# io-board-d-1.net
KiCad netlist of a schematic drawn in EAGLE
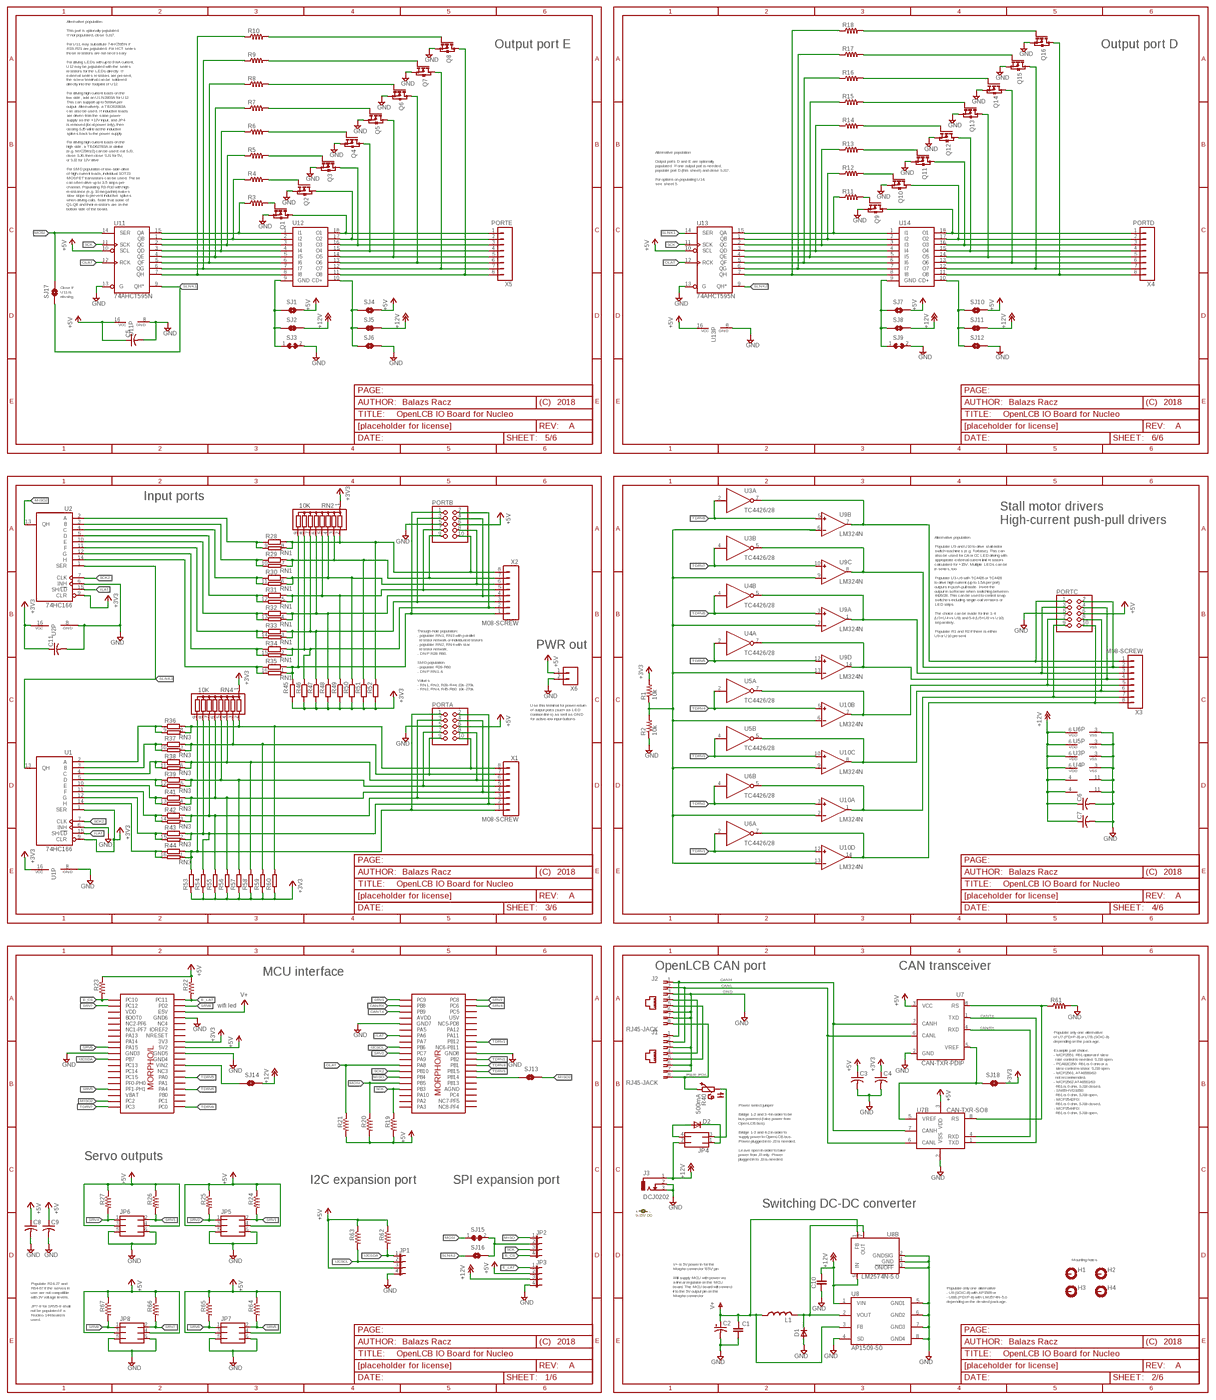
[diagram p0: schematic, sheet 1, overview]
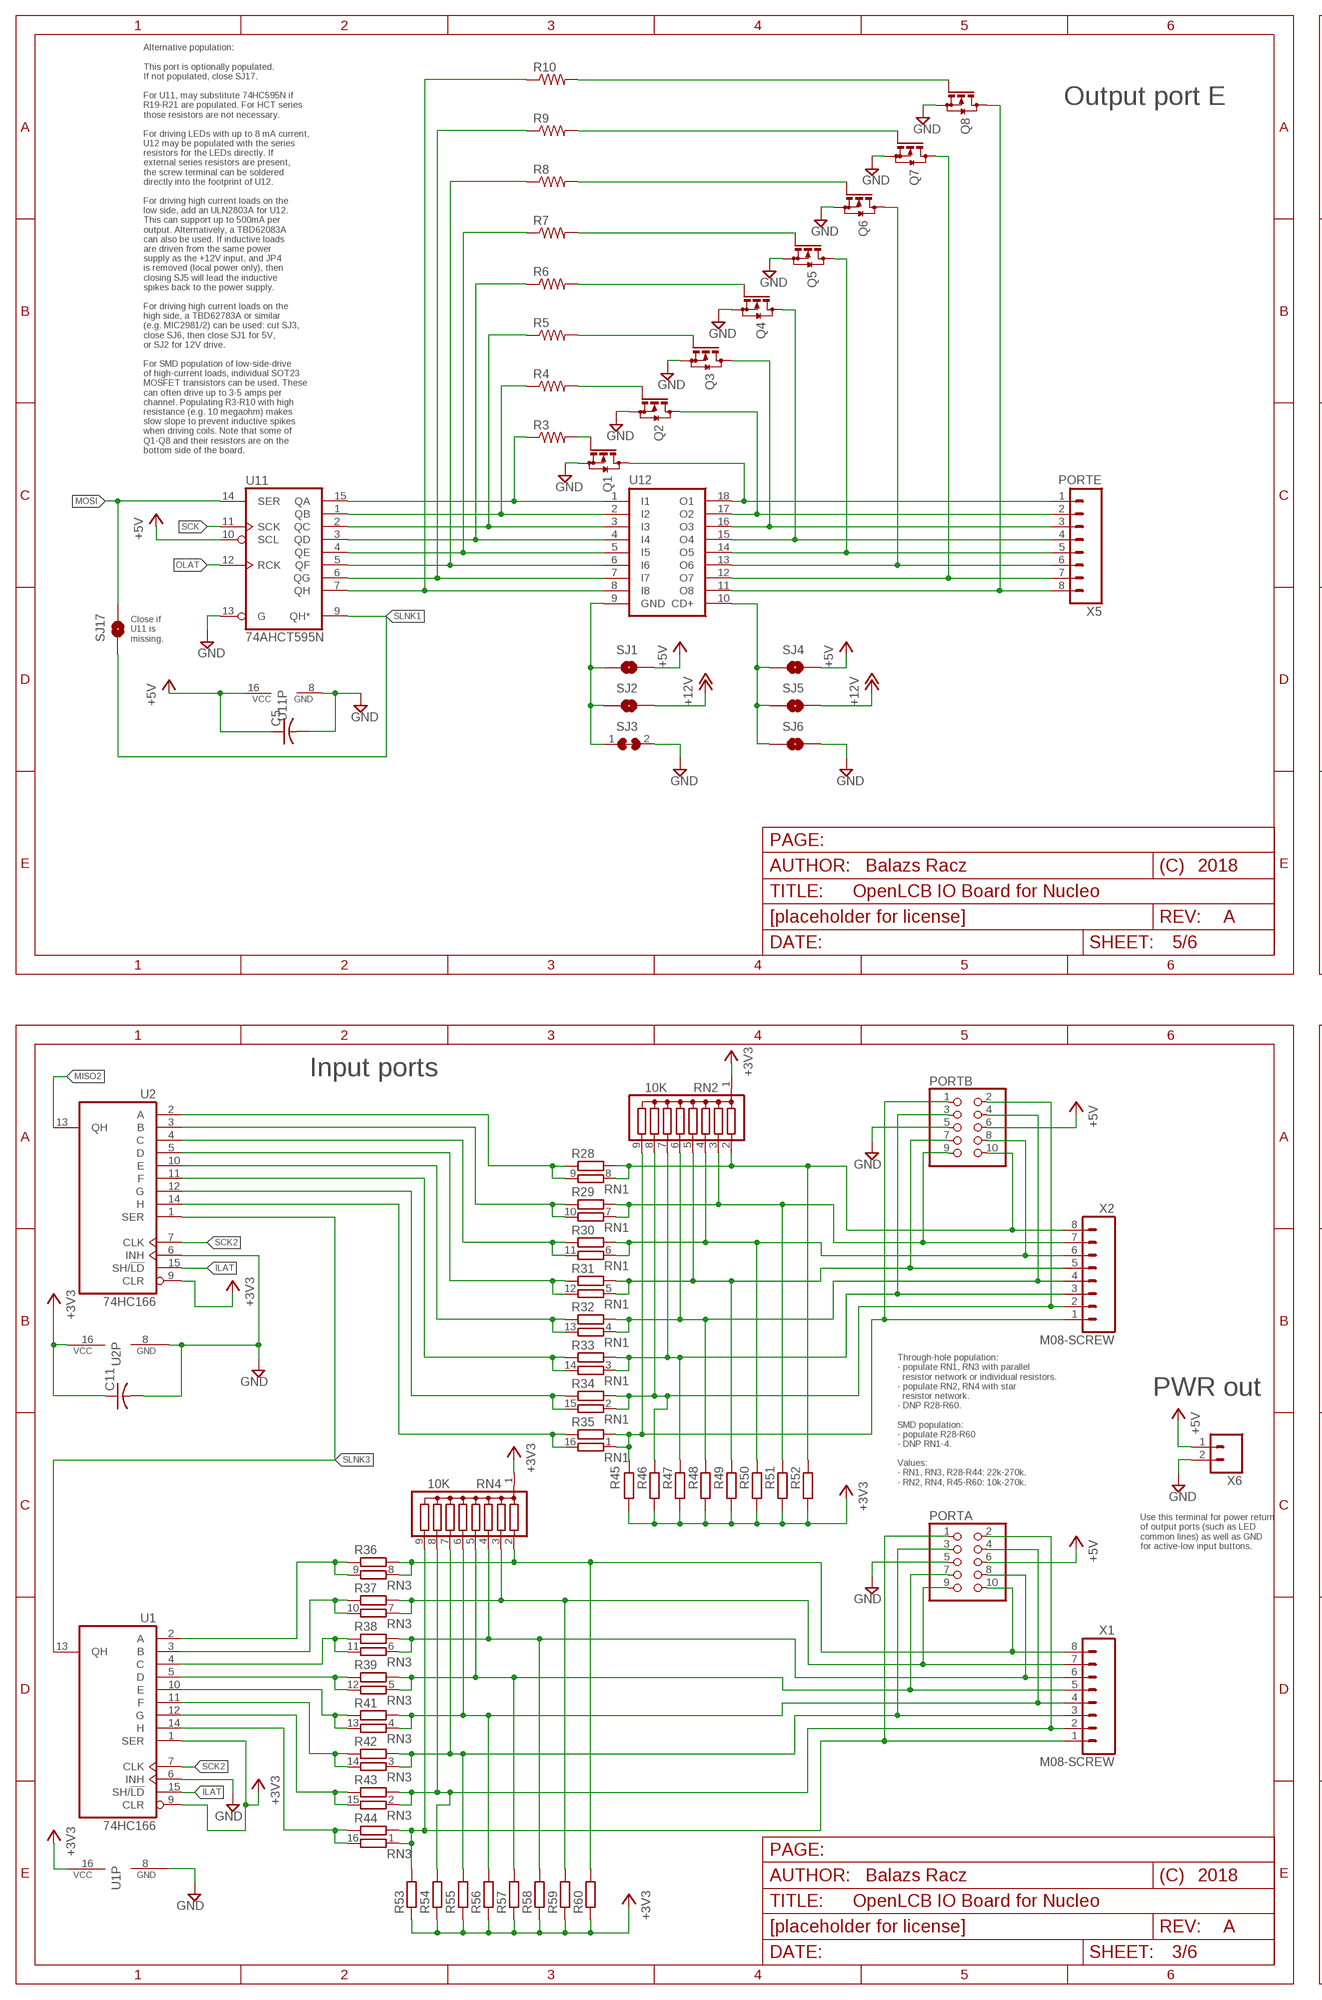
[diagram p1: schematic, sheet 1, part 1 of 4]
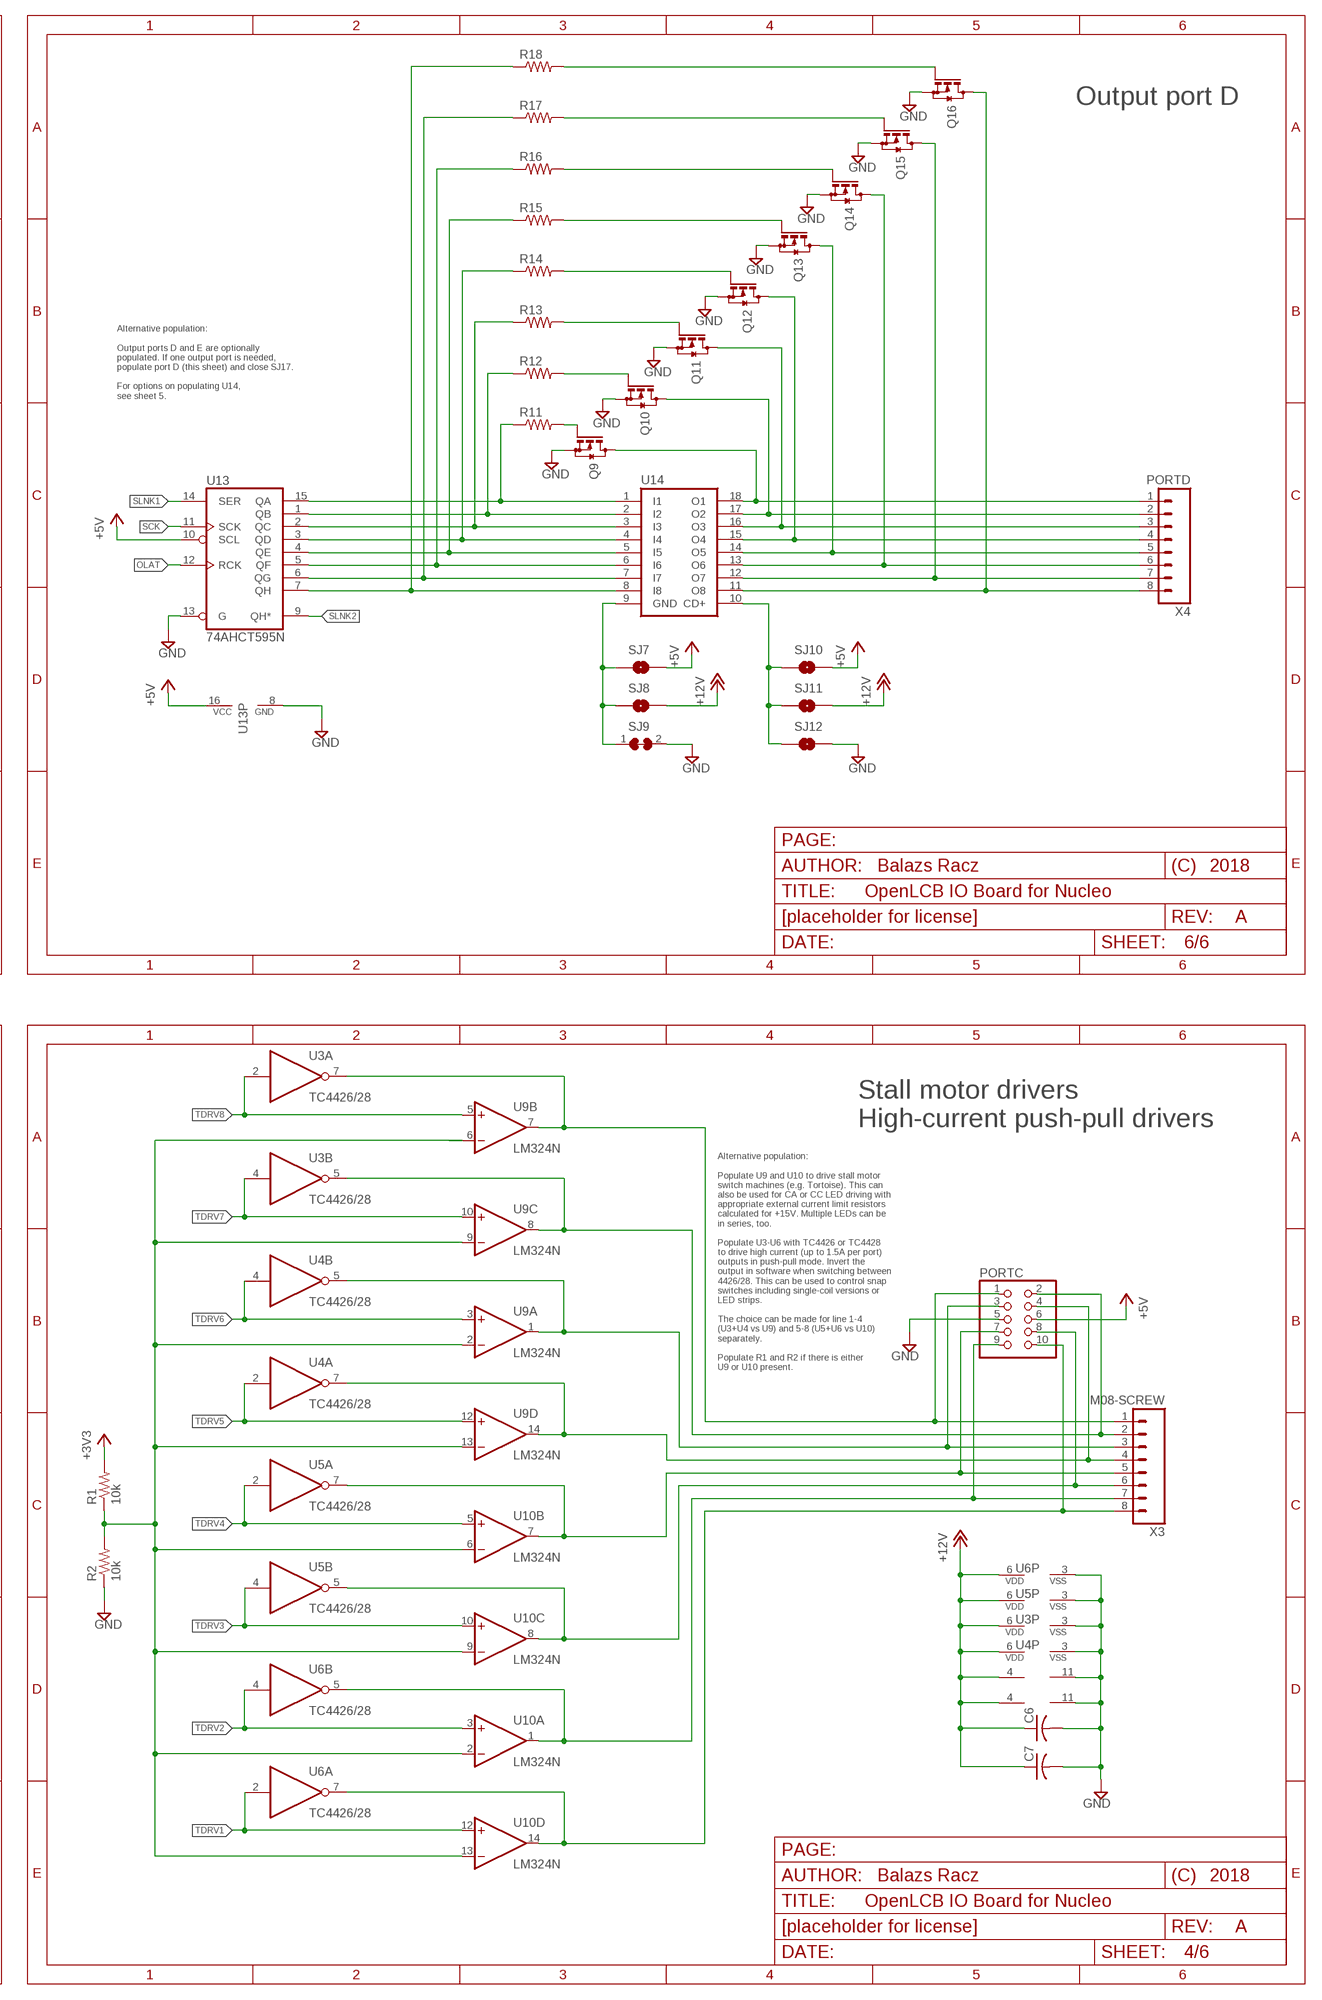
[diagram p2: schematic, sheet 1, part 2 of 4]
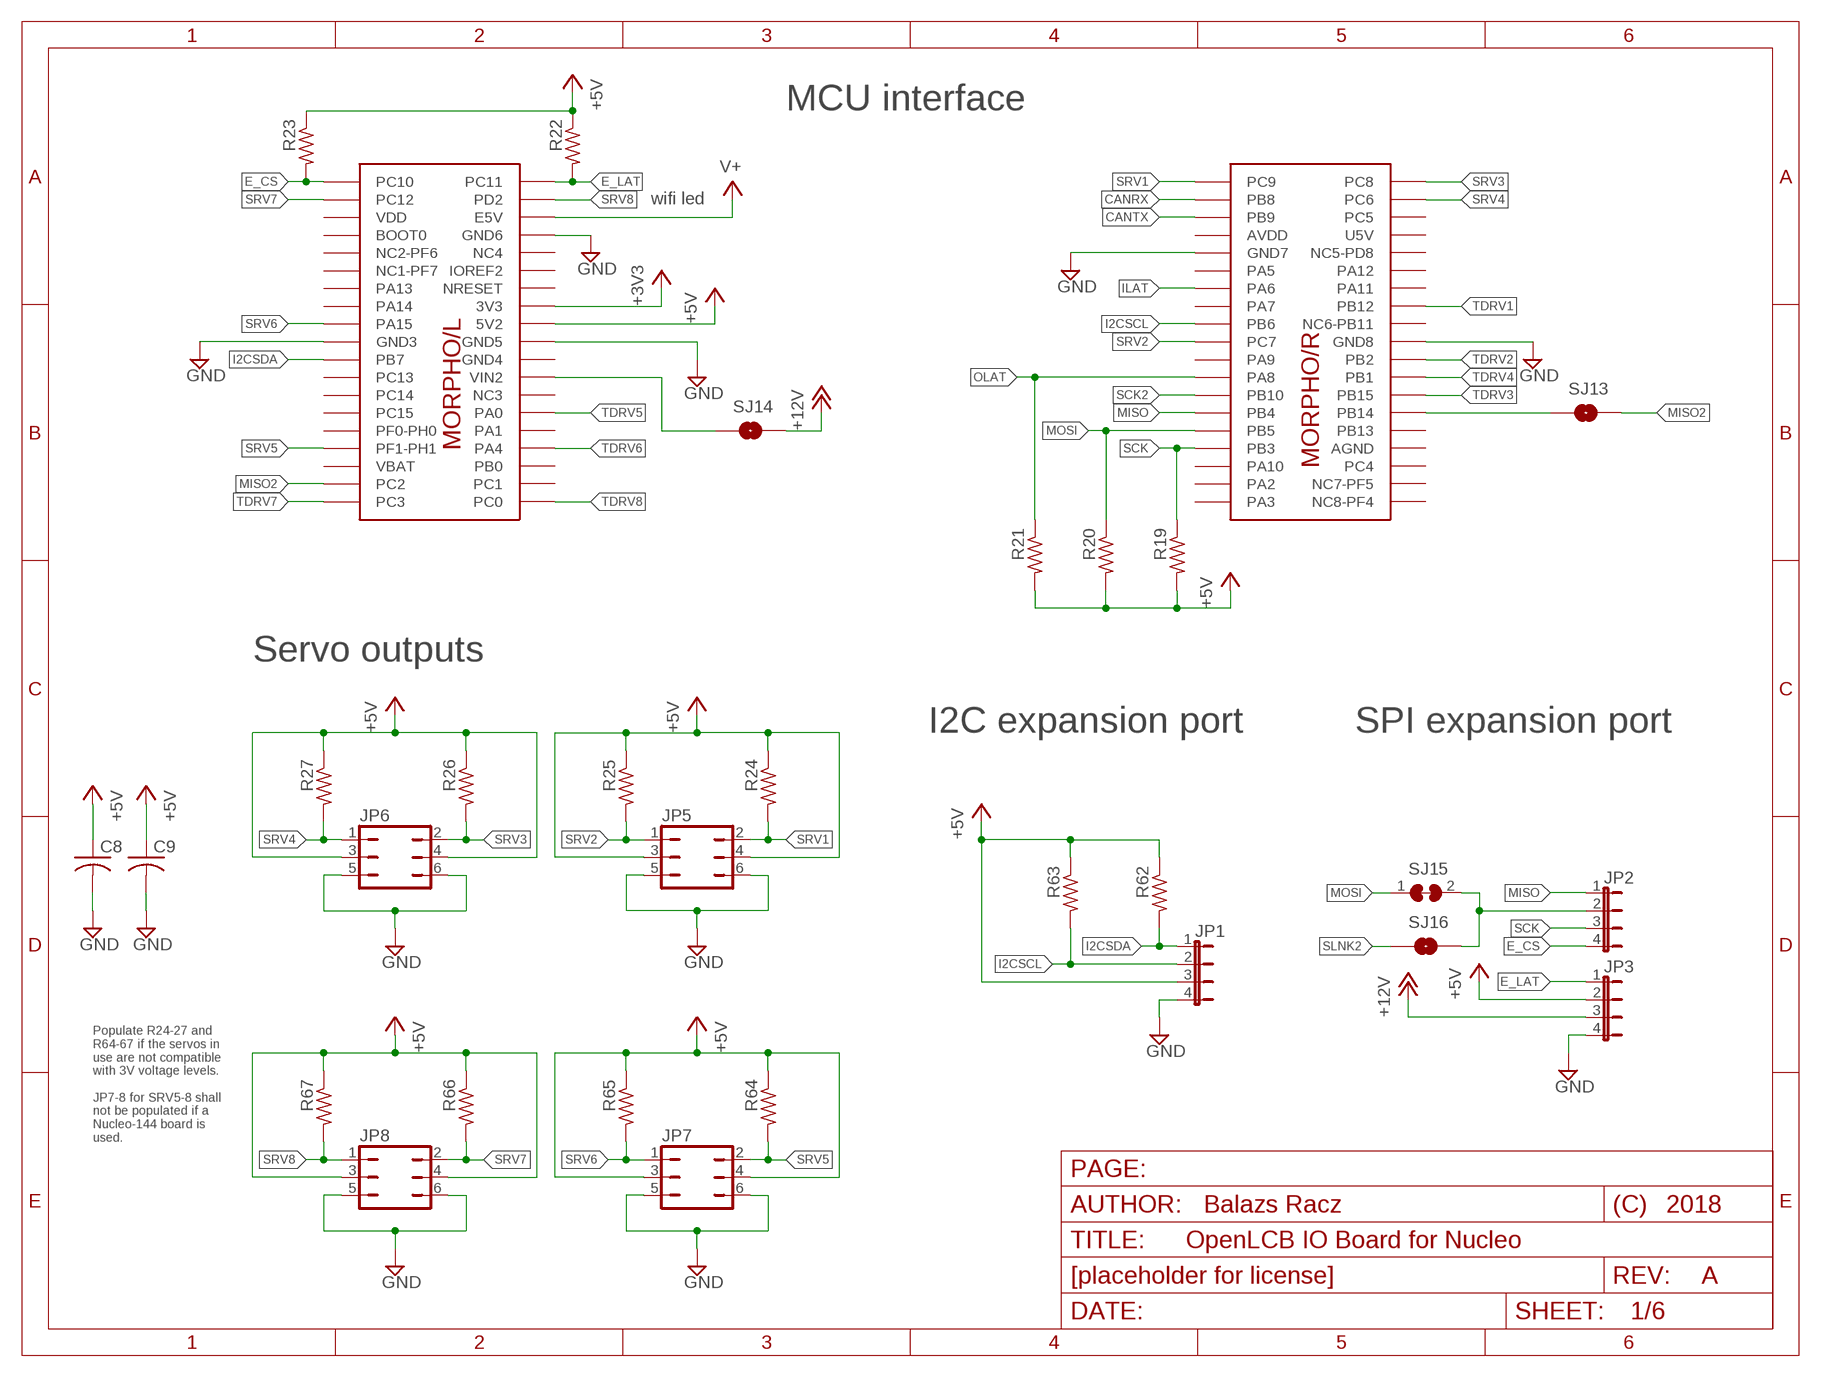
[diagram p3: schematic, sheet 1, part 3 of 4]
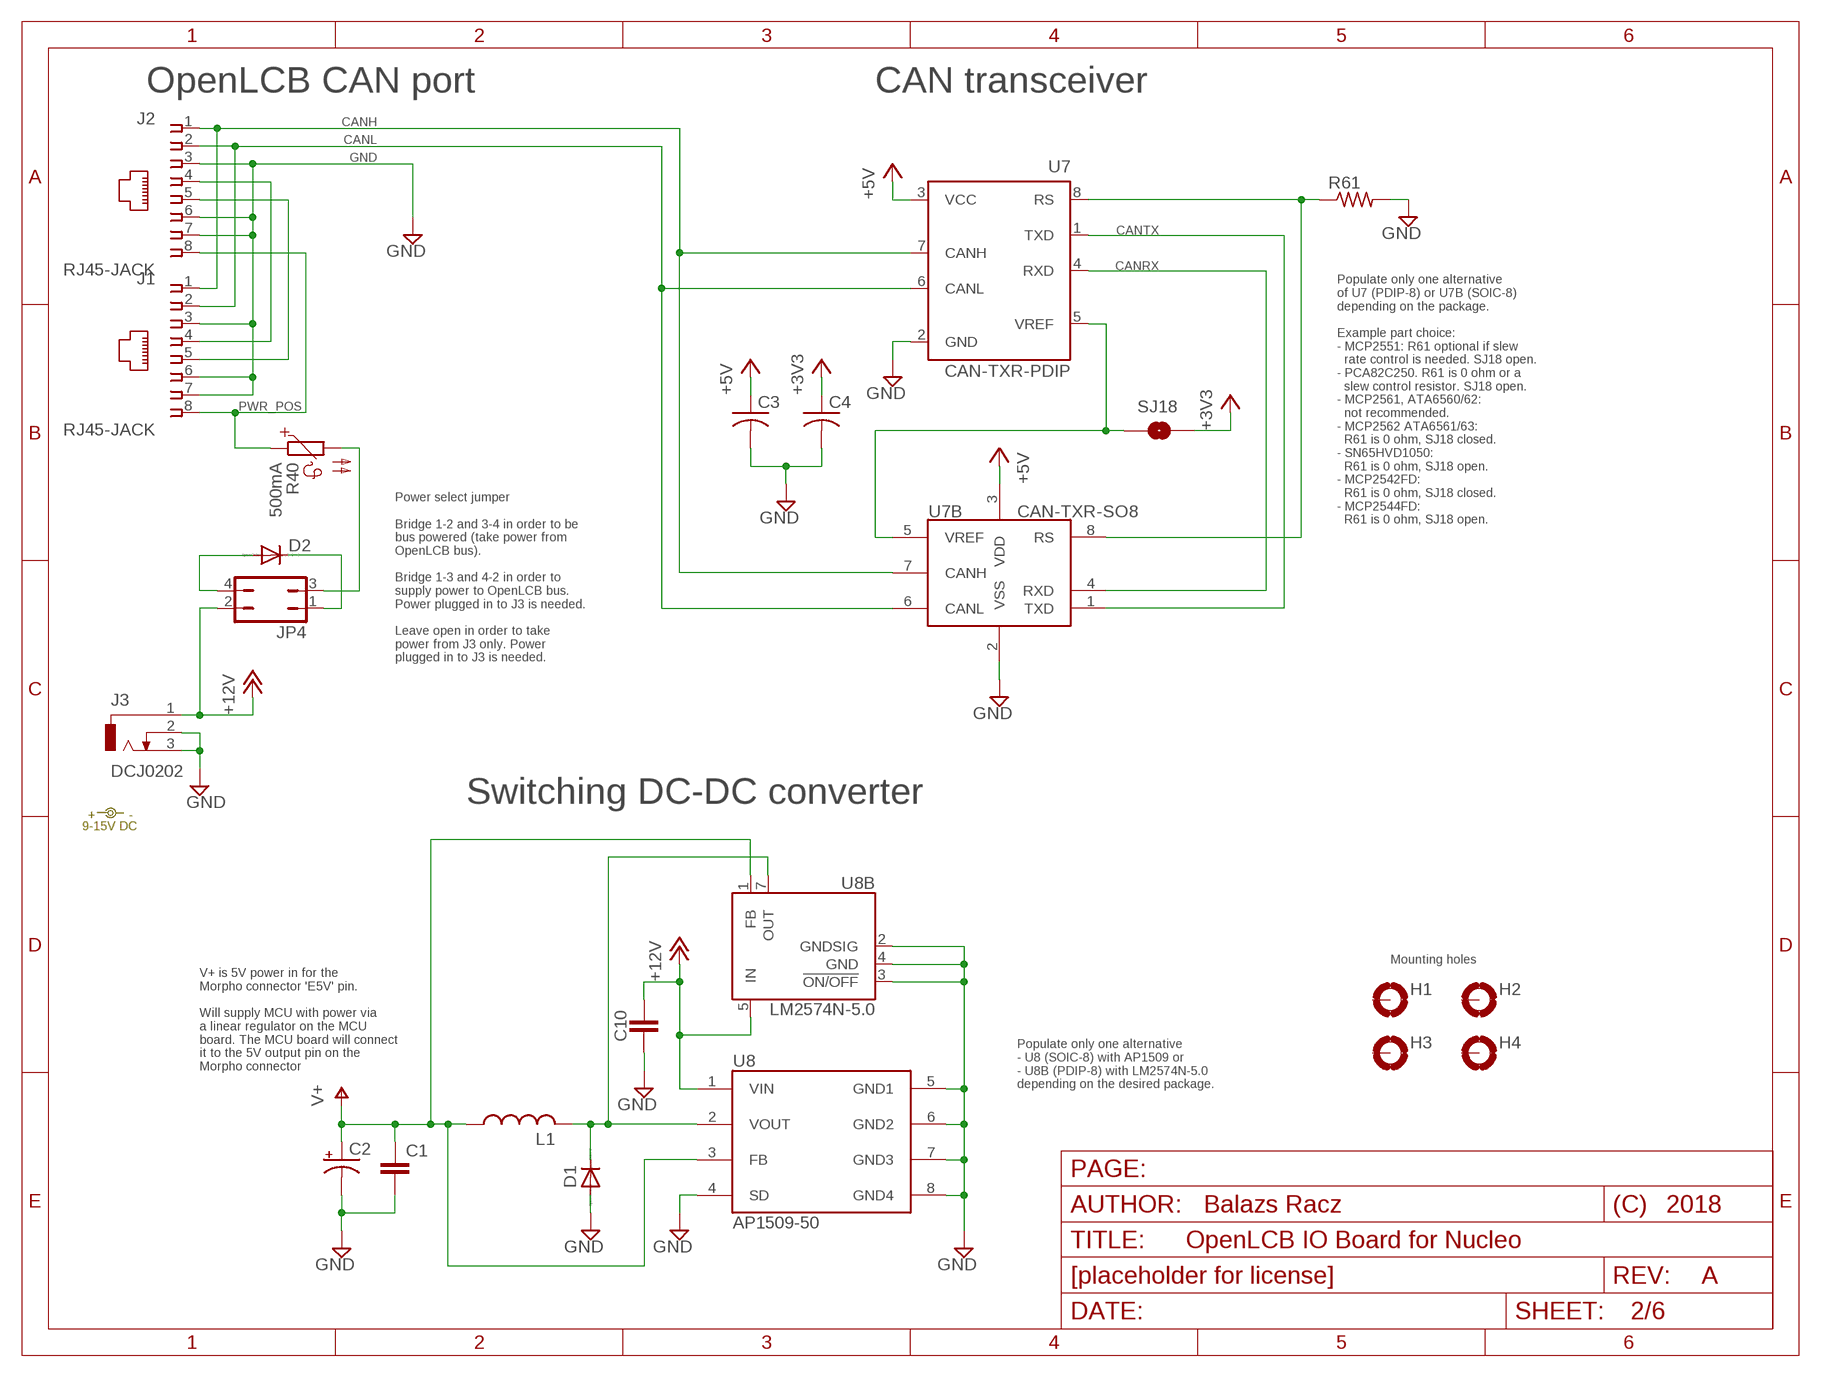
[diagram p4: schematic, sheet 1, part 4 of 4]

(export (version "E")
  (design (tool "Eeschema 10.0.6"))
  (components
    (comp (ref "+12V")
      (value "9-15V DC")
      (footprint "eagle-import:POWER_USAGE")
      (libsource (lib "eagle-import") (part "DOC-POWER_LABEL"))
    )
    (comp (ref "C1")
      (value "C-EUC1206")
      (footprint "eagle-import:C1206")
      (libsource (lib "eagle-import") (part "C-EUC1206"))
    )
    (comp (ref "C2")
      (value "CPOL-USE2.5-5")
      (footprint "eagle-import:E2,5-5")
      (libsource (lib "eagle-import") (part "CPOL-USE2.5-5"))
    )
    (comp (ref "C3")
      (value "C-USC0805")
      (footprint "eagle-import:C0805")
      (libsource (lib "eagle-import") (part "C-USC0805"))
    )
    (comp (ref "C4")
      (value "C-USC0805")
      (footprint "eagle-import:C0805")
      (libsource (lib "eagle-import") (part "C-USC0805"))
    )
    (comp (ref "C5")
      (value "C-USC0805")
      (footprint "eagle-import:C0805")
      (libsource (lib "eagle-import") (part "C-USC0805"))
    )
    (comp (ref "C6")
      (value "C-USC1206")
      (footprint "eagle-import:C1206")
      (libsource (lib "eagle-import") (part "C-USC1206"))
    )
    (comp (ref "C7")
      (value "C-USC1206")
      (footprint "eagle-import:C1206")
      (libsource (lib "eagle-import") (part "C-USC1206"))
    )
    (comp (ref "C8")
      (value "C-USC1206")
      (footprint "eagle-import:C1206")
      (libsource (lib "eagle-import") (part "C-USC1206"))
    )
    (comp (ref "C9")
      (value "C-USC1206")
      (footprint "eagle-import:C1206")
      (libsource (lib "eagle-import") (part "C-USC1206"))
    )
    (comp (ref "C10")
      (value "C-EUC1206")
      (footprint "eagle-import:C1206")
      (libsource (lib "eagle-import") (part "C-EUC1206"))
    )
    (comp (ref "C11")
      (value "C-USC0805")
      (footprint "eagle-import:C0805")
      (libsource (lib "eagle-import") (part "C-USC0805"))
    )
    (comp (ref "D1")
      (value "DIODE-DO41-7.6")
      (footprint "eagle-import:DO41-7.6")
      (libsource (lib "eagle-import") (part "DIODE-DO41-7.6"))
    )
    (comp (ref "D2")
      (value "DIODE-DO41-7.6")
      (footprint "eagle-import:DO41-7.6")
      (libsource (lib "eagle-import") (part "DIODE-DO41-7.6"))
    )
    (comp (ref "H1")
      (value "MOUNT-PAD-ROUND3.3")
      (footprint "eagle-import:3,3-PAD")
      (libsource (lib "eagle-import") (part "MOUNT-PAD-ROUND3.3"))
    )
    (comp (ref "H2")
      (value "MOUNT-PAD-ROUND3.3")
      (footprint "eagle-import:3,3-PAD")
      (libsource (lib "eagle-import") (part "MOUNT-PAD-ROUND3.3"))
    )
    (comp (ref "H3")
      (value "MOUNT-PAD-ROUND3.3")
      (footprint "eagle-import:3,3-PAD")
      (libsource (lib "eagle-import") (part "MOUNT-PAD-ROUND3.3"))
    )
    (comp (ref "H4")
      (value "MOUNT-PAD-ROUND3.3")
      (footprint "eagle-import:3,3-PAD")
      (libsource (lib "eagle-import") (part "MOUNT-PAD-ROUND3.3"))
    )
    (comp (ref "J1")
      (value "RJ45-JACK")
      (footprint "eagle-import:RJ45-PULSE-E5J88")
      (libsource (lib "eagle-import") (part "RJ45-JACKRJ45-PULSE-E5J00"))
    )
    (comp (ref "J2")
      (value "RJ45-JACK")
      (footprint "eagle-import:RJ45-PULSE-E5J88")
      (libsource (lib "eagle-import") (part "RJ45-JACKRJ45-PULSE-E5J00"))
    )
    (comp (ref "J3")
      (value "DCJ0202")
      (footprint "eagle-import:DCJ0202")
      (libsource (lib "eagle-import") (part "DCJ0202"))
    )
    (comp (ref "JP1")
      (value "JP4-FLAT")
      (footprint "eagle-import:JP4F")
      (libsource (lib "eagle-import") (part "JP4-FLAT"))
    )
    (comp (ref "JP2")
      (value "JP4-FLAT")
      (footprint "eagle-import:JP4F")
      (libsource (lib "eagle-import") (part "JP4-FLAT"))
    )
    (comp (ref "JP3")
      (value "JP4-FLAT")
      (footprint "eagle-import:JP4F")
      (libsource (lib "eagle-import") (part "JP4-FLAT"))
    )
    (comp (ref "JP4")
      (value "JP2Q")
      (footprint "eagle-import:JP2Q")
      (libsource (lib "eagle-import") (part "JP2Q"))
    )
    (comp (ref "JP5")
      (value "JP3Q")
      (footprint "eagle-import:JP3Q")
      (libsource (lib "eagle-import") (part "JP3Q"))
    )
    (comp (ref "JP6")
      (value "JP3Q")
      (footprint "eagle-import:JP3Q")
      (libsource (lib "eagle-import") (part "JP3Q"))
    )
    (comp (ref "JP7")
      (value "JP3Q")
      (footprint "eagle-import:JP3Q")
      (libsource (lib "eagle-import") (part "JP3Q"))
    )
    (comp (ref "JP8")
      (value "JP3Q")
      (footprint "eagle-import:JP3Q")
      (libsource (lib "eagle-import") (part "JP3Q"))
    )
    (comp (ref "L1")
      (value "L-US")
      (footprint "eagle-import:L5-8,5")
      (libsource (lib "eagle-import") (part "L-US"))
    )
    (comp (ref "PORTA")
      (value "PINHD-2X5CN")
      (footprint "eagle-import:CON10M")
      (libsource (lib "eagle-import") (part "PINHD-2X5CN"))
    )
    (comp (ref "PORTB")
      (value "PINHD-2X5CN")
      (footprint "eagle-import:CON10M")
      (libsource (lib "eagle-import") (part "PINHD-2X5CN"))
    )
    (comp (ref "PORTC")
      (value "PINHD-2X5CN")
      (footprint "eagle-import:CON10M")
      (libsource (lib "eagle-import") (part "PINHD-2X5CN"))
    )
    (comp (ref "Q1")
      (value "BSS123")
      (footprint "eagle-import:SOT23")
      (libsource (lib "eagle-import") (part "BSS123"))
    )
    (comp (ref "Q2")
      (value "BSS123")
      (footprint "eagle-import:SOT23")
      (libsource (lib "eagle-import") (part "BSS123"))
    )
    (comp (ref "Q3")
      (value "BSS123")
      (footprint "eagle-import:SOT23")
      (libsource (lib "eagle-import") (part "BSS123"))
    )
    (comp (ref "Q4")
      (value "BSS123")
      (footprint "eagle-import:SOT23")
      (libsource (lib "eagle-import") (part "BSS123"))
    )
    (comp (ref "Q5")
      (value "BSS123")
      (footprint "eagle-import:SOT23")
      (libsource (lib "eagle-import") (part "BSS123"))
    )
    (comp (ref "Q6")
      (value "BSS123")
      (footprint "eagle-import:SOT23")
      (libsource (lib "eagle-import") (part "BSS123"))
    )
    (comp (ref "Q7")
      (value "BSS123")
      (footprint "eagle-import:SOT23")
      (libsource (lib "eagle-import") (part "BSS123"))
    )
    (comp (ref "Q8")
      (value "BSS123")
      (footprint "eagle-import:SOT23")
      (libsource (lib "eagle-import") (part "BSS123"))
    )
    (comp (ref "Q9")
      (value "BSS123")
      (footprint "eagle-import:SOT23")
      (libsource (lib "eagle-import") (part "BSS123"))
    )
    (comp (ref "Q10")
      (value "BSS123")
      (footprint "eagle-import:SOT23")
      (libsource (lib "eagle-import") (part "BSS123"))
    )
    (comp (ref "Q11")
      (value "BSS123")
      (footprint "eagle-import:SOT23")
      (libsource (lib "eagle-import") (part "BSS123"))
    )
    (comp (ref "Q12")
      (value "BSS123")
      (footprint "eagle-import:SOT23")
      (libsource (lib "eagle-import") (part "BSS123"))
    )
    (comp (ref "Q13")
      (value "BSS123")
      (footprint "eagle-import:SOT23")
      (libsource (lib "eagle-import") (part "BSS123"))
    )
    (comp (ref "Q14")
      (value "BSS123")
      (footprint "eagle-import:SOT23")
      (libsource (lib "eagle-import") (part "BSS123"))
    )
    (comp (ref "Q15")
      (value "BSS123")
      (footprint "eagle-import:SOT23")
      (libsource (lib "eagle-import") (part "BSS123"))
    )
    (comp (ref "Q16")
      (value "BSS123")
      (footprint "eagle-import:SOT23")
      (libsource (lib "eagle-import") (part "BSS123"))
    )
    (comp (ref "R1")
      (value "10k")
      (footprint "eagle-import:R0805")
      (libsource (lib "eagle-import") (part "R-US_R0805"))
    )
    (comp (ref "R2")
      (value "10k")
      (footprint "eagle-import:R0805")
      (libsource (lib "eagle-import") (part "R-US_R0805"))
    )
    (comp (ref "R3")
      (value "R-US_R0603")
      (footprint "eagle-import:R0603")
      (libsource (lib "eagle-import") (part "R-US_R0603"))
    )
    (comp (ref "R4")
      (value "R-US_R0603")
      (footprint "eagle-import:R0603")
      (libsource (lib "eagle-import") (part "R-US_R0603"))
    )
    (comp (ref "R5")
      (value "R-US_R0603")
      (footprint "eagle-import:R0603")
      (libsource (lib "eagle-import") (part "R-US_R0603"))
    )
    (comp (ref "R6")
      (value "R-US_R0603")
      (footprint "eagle-import:R0603")
      (libsource (lib "eagle-import") (part "R-US_R0603"))
    )
    (comp (ref "R7")
      (value "R-US_R0603")
      (footprint "eagle-import:R0603")
      (libsource (lib "eagle-import") (part "R-US_R0603"))
    )
    (comp (ref "R8")
      (value "R-US_R0603")
      (footprint "eagle-import:R0603")
      (libsource (lib "eagle-import") (part "R-US_R0603"))
    )
    (comp (ref "R9")
      (value "R-US_R0603")
      (footprint "eagle-import:R0603")
      (libsource (lib "eagle-import") (part "R-US_R0603"))
    )
    (comp (ref "R10")
      (value "R-US_R0603")
      (footprint "eagle-import:R0603")
      (libsource (lib "eagle-import") (part "R-US_R0603"))
    )
    (comp (ref "R11")
      (value "R-US_R0603")
      (footprint "eagle-import:R0603")
      (libsource (lib "eagle-import") (part "R-US_R0603"))
    )
    (comp (ref "R12")
      (value "R-US_R0603")
      (footprint "eagle-import:R0603")
      (libsource (lib "eagle-import") (part "R-US_R0603"))
    )
    (comp (ref "R13")
      (value "R-US_R0603")
      (footprint "eagle-import:R0603")
      (libsource (lib "eagle-import") (part "R-US_R0603"))
    )
    (comp (ref "R14")
      (value "R-US_R0603")
      (footprint "eagle-import:R0603")
      (libsource (lib "eagle-import") (part "R-US_R0603"))
    )
    (comp (ref "R15")
      (value "R-US_R0603")
      (footprint "eagle-import:R0603")
      (libsource (lib "eagle-import") (part "R-US_R0603"))
    )
    (comp (ref "R16")
      (value "R-US_R0603")
      (footprint "eagle-import:R0603")
      (libsource (lib "eagle-import") (part "R-US_R0603"))
    )
    (comp (ref "R17")
      (value "R-US_R0603")
      (footprint "eagle-import:R0603")
      (libsource (lib "eagle-import") (part "R-US_R0603"))
    )
    (comp (ref "R18")
      (value "R-US_R0603")
      (footprint "eagle-import:R0603")
      (libsource (lib "eagle-import") (part "R-US_R0603"))
    )
    (comp (ref "R19")
      (value "R-US_R0805")
      (footprint "eagle-import:R0805")
      (libsource (lib "eagle-import") (part "rcl_334_R-US_R0805"))
    )
    (comp (ref "R20")
      (value "R-US_R0805")
      (footprint "eagle-import:R0805")
      (libsource (lib "eagle-import") (part "rcl_334_R-US_R0805"))
    )
    (comp (ref "R21")
      (value "R-US_R0805")
      (footprint "eagle-import:R0805")
      (libsource (lib "eagle-import") (part "rcl_334_R-US_R0805"))
    )
    (comp (ref "R22")
      (value "R-US_R0805")
      (footprint "eagle-import:R0805")
      (libsource (lib "eagle-import") (part "rcl_334_R-US_R0805"))
    )
    (comp (ref "R23")
      (value "R-US_R0805")
      (footprint "eagle-import:R0805")
      (libsource (lib "eagle-import") (part "rcl_334_R-US_R0805"))
    )
    (comp (ref "R24")
      (value "R-US_R0805")
      (footprint "eagle-import:R0805")
      (libsource (lib "eagle-import") (part "rcl_334_R-US_R0805"))
    )
    (comp (ref "R25")
      (value "R-US_R0805")
      (footprint "eagle-import:R0805")
      (libsource (lib "eagle-import") (part "rcl_334_R-US_R0805"))
    )
    (comp (ref "R26")
      (value "R-US_R0805")
      (footprint "eagle-import:R0805")
      (libsource (lib "eagle-import") (part "rcl_334_R-US_R0805"))
    )
    (comp (ref "R27")
      (value "R-US_R0805")
      (footprint "eagle-import:R0805")
      (libsource (lib "eagle-import") (part "rcl_334_R-US_R0805"))
    )
    (comp (ref "R28")
      (value "R-EU_R0603")
      (footprint "eagle-import:R0603")
      (libsource (lib "eagle-import") (part "R-EU_R0603"))
    )
    (comp (ref "R29")
      (value "R-EU_R0603")
      (footprint "eagle-import:R0603")
      (libsource (lib "eagle-import") (part "R-EU_R0603"))
    )
    (comp (ref "R30")
      (value "R-EU_R0603")
      (footprint "eagle-import:R0603")
      (libsource (lib "eagle-import") (part "R-EU_R0603"))
    )
    (comp (ref "R31")
      (value "R-EU_R0603")
      (footprint "eagle-import:R0603")
      (libsource (lib "eagle-import") (part "R-EU_R0603"))
    )
    (comp (ref "R32")
      (value "R-EU_R0603")
      (footprint "eagle-import:R0603")
      (libsource (lib "eagle-import") (part "R-EU_R0603"))
    )
    (comp (ref "R33")
      (value "R-EU_R0603")
      (footprint "eagle-import:R0603")
      (libsource (lib "eagle-import") (part "R-EU_R0603"))
    )
    (comp (ref "R34")
      (value "R-EU_R0603")
      (footprint "eagle-import:R0603")
      (libsource (lib "eagle-import") (part "R-EU_R0603"))
    )
    (comp (ref "R35")
      (value "R-EU_R0603")
      (footprint "eagle-import:R0603")
      (libsource (lib "eagle-import") (part "R-EU_R0603"))
    )
    (comp (ref "R36")
      (value "R-EU_R0603")
      (footprint "eagle-import:R0603")
      (libsource (lib "eagle-import") (part "R-EU_R0603"))
    )
    (comp (ref "R37")
      (value "R-EU_R0603")
      (footprint "eagle-import:R0603")
      (libsource (lib "eagle-import") (part "R-EU_R0603"))
    )
    (comp (ref "R38")
      (value "R-EU_R0603")
      (footprint "eagle-import:R0603")
      (libsource (lib "eagle-import") (part "R-EU_R0603"))
    )
    (comp (ref "R39")
      (value "R-EU_R0603")
      (footprint "eagle-import:R0603")
      (libsource (lib "eagle-import") (part "R-EU_R0603"))
    )
    (comp (ref "R40")
      (value "500mA")
      (footprint "eagle-import:PTC1812")
      (libsource (lib "eagle-import") (part "PTC_1812"))
    )
    (comp (ref "R41")
      (value "R-EU_R0603")
      (footprint "eagle-import:R0603")
      (libsource (lib "eagle-import") (part "R-EU_R0603"))
    )
    (comp (ref "R42")
      (value "R-EU_R0603")
      (footprint "eagle-import:R0603")
      (libsource (lib "eagle-import") (part "R-EU_R0603"))
    )
    (comp (ref "R43")
      (value "R-EU_R0603")
      (footprint "eagle-import:R0603")
      (libsource (lib "eagle-import") (part "R-EU_R0603"))
    )
    (comp (ref "R44")
      (value "R-EU_R0603")
      (footprint "eagle-import:R0603")
      (libsource (lib "eagle-import") (part "R-EU_R0603"))
    )
    (comp (ref "R45")
      (value "R-EU_R0603")
      (footprint "eagle-import:R0603")
      (libsource (lib "eagle-import") (part "R-EU_R0603"))
    )
    (comp (ref "R46")
      (value "R-EU_R0603")
      (footprint "eagle-import:R0603")
      (libsource (lib "eagle-import") (part "R-EU_R0603"))
    )
    (comp (ref "R47")
      (value "R-EU_R0603")
      (footprint "eagle-import:R0603")
      (libsource (lib "eagle-import") (part "R-EU_R0603"))
    )
    (comp (ref "R48")
      (value "R-EU_R0603")
      (footprint "eagle-import:R0603")
      (libsource (lib "eagle-import") (part "R-EU_R0603"))
    )
    (comp (ref "R49")
      (value "R-EU_R0603")
      (footprint "eagle-import:R0603")
      (libsource (lib "eagle-import") (part "R-EU_R0603"))
    )
    (comp (ref "R50")
      (value "R-EU_R0603")
      (footprint "eagle-import:R0603")
      (libsource (lib "eagle-import") (part "R-EU_R0603"))
    )
    (comp (ref "R51")
      (value "R-EU_R0603")
      (footprint "eagle-import:R0603")
      (libsource (lib "eagle-import") (part "R-EU_R0603"))
    )
    (comp (ref "R52")
      (value "R-EU_R0603")
      (footprint "eagle-import:R0603")
      (libsource (lib "eagle-import") (part "R-EU_R0603"))
    )
    (comp (ref "R53")
      (value "R-EU_R0603")
      (footprint "eagle-import:R0603")
      (libsource (lib "eagle-import") (part "R-EU_R0603"))
    )
    (comp (ref "R54")
      (value "R-EU_R0603")
      (footprint "eagle-import:R0603")
      (libsource (lib "eagle-import") (part "R-EU_R0603"))
    )
    (comp (ref "R55")
      (value "R-EU_R0603")
      (footprint "eagle-import:R0603")
      (libsource (lib "eagle-import") (part "R-EU_R0603"))
    )
    (comp (ref "R56")
      (value "R-EU_R0603")
      (footprint "eagle-import:R0603")
      (libsource (lib "eagle-import") (part "R-EU_R0603"))
    )
    (comp (ref "R57")
      (value "R-EU_R0603")
      (footprint "eagle-import:R0603")
      (libsource (lib "eagle-import") (part "R-EU_R0603"))
    )
    (comp (ref "R58")
      (value "R-EU_R0603")
      (footprint "eagle-import:R0603")
      (libsource (lib "eagle-import") (part "R-EU_R0603"))
    )
    (comp (ref "R59")
      (value "R-EU_R0603")
      (footprint "eagle-import:R0603")
      (libsource (lib "eagle-import") (part "R-EU_R0603"))
    )
    (comp (ref "R60")
      (value "R-EU_R0603")
      (footprint "eagle-import:R0603")
      (libsource (lib "eagle-import") (part "R-EU_R0603"))
    )
    (comp (ref "R61")
      (value "R-US_R0805")
      (footprint "eagle-import:R0805")
      (libsource (lib "eagle-import") (part "rcl_334_R-US_R0805"))
    )
    (comp (ref "R62")
      (value "R-US_R0805")
      (footprint "eagle-import:R0805")
      (libsource (lib "eagle-import") (part "rcl_334_R-US_R0805"))
    )
    (comp (ref "R63")
      (value "R-US_R0805")
      (footprint "eagle-import:R0805")
      (libsource (lib "eagle-import") (part "rcl_334_R-US_R0805"))
    )
    (comp (ref "R64")
      (value "R-US_R0805")
      (footprint "eagle-import:R0805")
      (libsource (lib "eagle-import") (part "rcl_334_R-US_R0805"))
    )
    (comp (ref "R65")
      (value "R-US_R0805")
      (footprint "eagle-import:R0805")
      (libsource (lib "eagle-import") (part "rcl_334_R-US_R0805"))
    )
    (comp (ref "R66")
      (value "R-US_R0805")
      (footprint "eagle-import:R0805")
      (libsource (lib "eagle-import") (part "rcl_334_R-US_R0805"))
    )
    (comp (ref "R67")
      (value "R-US_R0805")
      (footprint "eagle-import:R0805")
      (libsource (lib "eagle-import") (part "rcl_334_R-US_R0805"))
    )
    (comp (ref "RN1")
      (value "8R-P")
      (footprint "eagle-import:DIL16")
      (libsource (lib "eagle-import") (part "8R-P"))
    )
    (comp (ref "RN2")
      (value "10K")
      (footprint "eagle-import:SIL9")
      (libsource (lib "eagle-import") (part "G08R"))
    )
    (comp (ref "RN3")
      (value "8R-P")
      (footprint "eagle-import:DIL16")
      (libsource (lib "eagle-import") (part "8R-P"))
    )
    (comp (ref "RN4")
      (value "10K")
      (footprint "eagle-import:SIL9")
      (libsource (lib "eagle-import") (part "G08R"))
    )
    (comp (ref "SJ1")
      (value "SJRND2")
      (footprint "eagle-import:SJ_RND2")
      (libsource (lib "eagle-import") (part "SJRND2"))
    )
    (comp (ref "SJ2")
      (value "SJRND2")
      (footprint "eagle-import:SJ_RND2")
      (libsource (lib "eagle-import") (part "SJRND2"))
    )
    (comp (ref "SJ3")
      (value "SJ-C")
      (footprint "eagle-import:SJW-C")
      (libsource (lib "eagle-import") (part "SJ-C"))
    )
    (comp (ref "SJ4")
      (value "SJRND2")
      (footprint "eagle-import:SJ_RND2")
      (libsource (lib "eagle-import") (part "SJRND2"))
    )
    (comp (ref "SJ5")
      (value "SJRND2")
      (footprint "eagle-import:SJ_RND2")
      (libsource (lib "eagle-import") (part "SJRND2"))
    )
    (comp (ref "SJ6")
      (value "SJRND2")
      (footprint "eagle-import:SJ_RND2")
      (libsource (lib "eagle-import") (part "SJRND2"))
    )
    (comp (ref "SJ7")
      (value "SJRND2")
      (footprint "eagle-import:SJ_RND2")
      (libsource (lib "eagle-import") (part "SJRND2"))
    )
    (comp (ref "SJ8")
      (value "SJRND2")
      (footprint "eagle-import:SJ_RND2")
      (libsource (lib "eagle-import") (part "SJRND2"))
    )
    (comp (ref "SJ9")
      (value "SJ-C")
      (footprint "eagle-import:SJW-C")
      (libsource (lib "eagle-import") (part "SJ-C"))
    )
    (comp (ref "SJ10")
      (value "SJRND2")
      (footprint "eagle-import:SJ_RND2")
      (libsource (lib "eagle-import") (part "SJRND2"))
    )
    (comp (ref "SJ11")
      (value "SJRND2")
      (footprint "eagle-import:SJ_RND2")
      (libsource (lib "eagle-import") (part "SJRND2"))
    )
    (comp (ref "SJ12")
      (value "SJRND2")
      (footprint "eagle-import:SJ_RND2")
      (libsource (lib "eagle-import") (part "SJRND2"))
    )
    (comp (ref "SJ13")
      (value "SJRND2")
      (footprint "eagle-import:SJ_RND2")
      (libsource (lib "eagle-import") (part "SJRND2"))
    )
    (comp (ref "SJ14")
      (value "SJRND2")
      (footprint "eagle-import:SJ_RND2")
      (libsource (lib "eagle-import") (part "SJRND2"))
    )
    (comp (ref "SJ15")
      (value "SJ-C")
      (footprint "eagle-import:SJW-C")
      (libsource (lib "eagle-import") (part "SJ-C"))
    )
    (comp (ref "SJ16")
      (value "SJRND2")
      (footprint "eagle-import:SJ_RND2")
      (libsource (lib "eagle-import") (part "SJRND2"))
    )
    (comp (ref "SJ17")
      (value "SJRND2")
      (footprint "eagle-import:SJ_RND2")
      (libsource (lib "eagle-import") (part "SJRND2"))
    )
    (comp (ref "SJ18")
      (value "SJRND2")
      (footprint "eagle-import:SJ_RND2")
      (libsource (lib "eagle-import") (part "SJRND2"))
    )
    (comp (ref "U$1")
      (value "NUCLEO_64_GENERIC")
      (footprint "eagle-import:NUCLEO_BRD_BASE64")
      (libsource (lib "eagle-import") (part "NUCLEO_64_GENERIC"))
    )
    (comp (ref "U1")
      (value "74HC166")
      (footprint "eagle-import:DIL16")
      (libsource (lib "eagle-import") (part "74166N"))
    )
    (comp (ref "U2")
      (value "74HC166")
      (footprint "eagle-import:DIL16")
      (libsource (lib "eagle-import") (part "74166N"))
    )
    (comp (ref "U3")
      (value "TC4426/28")
      (footprint "eagle-import:DIL08-LONG")
      (libsource (lib "eagle-import") (part "TC4426APDIP"))
    )
    (comp (ref "U4")
      (value "TC4426/28")
      (footprint "eagle-import:DIL08-LONG")
      (libsource (lib "eagle-import") (part "TC4426APDIP"))
    )
    (comp (ref "U5")
      (value "TC4426/28")
      (footprint "eagle-import:DIL08-LONG")
      (libsource (lib "eagle-import") (part "TC4426APDIP"))
    )
    (comp (ref "U6")
      (value "TC4426/28")
      (footprint "eagle-import:DIL08-LONG")
      (libsource (lib "eagle-import") (part "TC4426APDIP"))
    )
    (comp (ref "U7")
      (value "CAN-TXR-PDIP")
      (footprint "eagle-import:DIL08")
      (libsource (lib "eagle-import") (part "PCA82C250"))
    )
    (comp (ref "U7B")
      (value "CAN-TXR-SO8")
      (footprint "eagle-import:SO-08")
      (libsource (lib "eagle-import") (part "MCP2551-SN"))
    )
    (comp (ref "U8")
      (value "AP1509-50")
      (footprint "eagle-import:SO-08")
      (libsource (lib "eagle-import") (part "AP1509"))
    )
    (comp (ref "U8B")
      (value "LM2574N-5.0")
      (footprint "eagle-import:DIL08")
      (libsource (lib "eagle-import") (part "LM2574?-N5.0"))
    )
    (comp (ref "U9")
      (value "LM324N")
      (footprint "eagle-import:DIL14")
      (libsource (lib "eagle-import") (part "LM324N"))
    )
    (comp (ref "U10")
      (value "LM324N")
      (footprint "eagle-import:DIL14")
      (libsource (lib "eagle-import") (part "LM324N"))
    )
    (comp (ref "U11")
      (value "74AHCT595N")
      (footprint "eagle-import:DIL16")
      (libsource (lib "eagle-import") (part "74595NHCT"))
    )
    (comp (ref "U12")
      (value "ULN2803A")
      (footprint "eagle-import:DIL18-THIN")
      (libsource (lib "eagle-import") (part "ULN2803A"))
    )
    (comp (ref "U13")
      (value "74AHCT595N")
      (footprint "eagle-import:DIL16")
      (libsource (lib "eagle-import") (part "74595NHCT"))
    )
    (comp (ref "U14")
      (value "ULN2803A")
      (footprint "eagle-import:DIL18-THIN")
      (libsource (lib "eagle-import") (part "ULN2803A"))
    )
    (comp (ref "X1")
      (value "M08-SCREW")
      (footprint "eagle-import:1X08_TERMINAL")
      (libsource (lib "eagle-import") (part "M08-SCREW"))
    )
    (comp (ref "X2")
      (value "M08-SCREW")
      (footprint "eagle-import:1X08_TERMINAL")
      (libsource (lib "eagle-import") (part "M08-SCREW"))
    )
    (comp (ref "X3")
      (value "M08-SCREW")
      (footprint "eagle-import:1X08_TERMINAL")
      (libsource (lib "eagle-import") (part "M08-SCREW"))
    )
    (comp (ref "X4")
      (value "PORTD")
      (footprint "eagle-import:1X08_TERMINAL")
      (libsource (lib "eagle-import") (part "M08-SCREW"))
    )
    (comp (ref "X5")
      (value "PORTE")
      (footprint "eagle-import:1X08_TERMINAL")
      (libsource (lib "eagle-import") (part "M08-SCREW"))
    )
    (comp (ref "X6")
      (value "CONNECTOR-M023.5MM-LOCK")
      (footprint "eagle-import:SCREWTERMINAL-3.5MM-2_LOCK")
      (libsource (lib "eagle-import") (part "CONNECTOR-M023.5MM-LOCK"))
    )
  )
  (nets
    (net (code "1") (name "+3V3") (class "Default")
      (node (ref "C11") (pin "1") (pinfunction "1_1") (pintype "passive"))
      (node (ref "C4") (pin "1") (pinfunction "1_1") (pintype "passive"))
      (node (ref "R1") (pin "2") (pinfunction "2_2") (pintype "passive"))
      (node (ref "R45") (pin "1") (pinfunction "1_1") (pintype "passive"))
      (node (ref "R46") (pin "2") (pinfunction "2_2") (pintype "passive"))
      (node (ref "R47") (pin "2") (pinfunction "2_2") (pintype "passive"))
      (node (ref "R48") (pin "2") (pinfunction "2_2") (pintype "passive"))
      (node (ref "R49") (pin "2") (pinfunction "2_2") (pintype "passive"))
      (node (ref "R50") (pin "2") (pinfunction "2_2") (pintype "passive"))
      (node (ref "R51") (pin "2") (pinfunction "2_2") (pintype "passive"))
      (node (ref "R52") (pin "2") (pinfunction "2_2") (pintype "passive"))
      (node (ref "R53") (pin "1") (pinfunction "1_1") (pintype "passive"))
      (node (ref "R54") (pin "1") (pinfunction "1_1") (pintype "passive"))
      (node (ref "R55") (pin "1") (pinfunction "1_1") (pintype "passive"))
      (node (ref "R56") (pin "1") (pinfunction "1_1") (pintype "passive"))
      (node (ref "R57") (pin "1") (pinfunction "1_1") (pintype "passive"))
      (node (ref "R58") (pin "1") (pinfunction "1_1") (pintype "passive"))
      (node (ref "R59") (pin "1") (pinfunction "1_1") (pintype "passive"))
      (node (ref "R60") (pin "1") (pinfunction "1_1") (pintype "passive"))
      (node (ref "RN2") (pin "1") (pinfunction "1_1") (pintype "passive"))
      (node (ref "RN4") (pin "1") (pinfunction "1_1") (pintype "passive"))
      (node (ref "SJ18") (pin "P$1") (pinfunction "1_P$1") (pintype "passive"))
      (node (ref "U$1") (pin "3V3") (pinfunction "3V3_3V3") (pintype "power_in"))
      (node (ref "U1") (pin "1") (pinfunction "SER_1") (pintype "input"))
      (node (ref "U1") (pin "16") (pinfunction "VCC_16") (pintype "power_in"))
      (node (ref "U1") (pin "9") (pinfunction "CLR_9") (pintype "input"))
      (node (ref "U2") (pin "16") (pinfunction "VCC_16") (pintype "power_in"))
      (node (ref "U2") (pin "9") (pinfunction "CLR_9") (pintype "input"))
    )
    (net (code "2") (name "+5V") (class "Default")
      (node (ref "C3") (pin "1") (pinfunction "1_1") (pintype "passive"))
      (node (ref "C5") (pin "1") (pinfunction "1_1") (pintype "passive"))
      (node (ref "C8") (pin "1") (pinfunction "1_1") (pintype "passive"))
      (node (ref "C9") (pin "1") (pinfunction "1_1") (pintype "passive"))
      (node (ref "JP1") (pin "3") (pinfunction "3_3") (pintype "passive"))
      (node (ref "JP3") (pin "2") (pinfunction "2_2") (pintype "passive"))
      (node (ref "JP5") (pin "3") (pinfunction "3_3") (pintype "passive"))
      (node (ref "JP5") (pin "4") (pinfunction "4_4") (pintype "passive"))
      (node (ref "JP6") (pin "3") (pinfunction "3_3") (pintype "passive"))
      (node (ref "JP6") (pin "4") (pinfunction "4_4") (pintype "passive"))
      (node (ref "JP7") (pin "3") (pinfunction "3_3") (pintype "passive"))
      (node (ref "JP7") (pin "4") (pinfunction "4_4") (pintype "passive"))
      (node (ref "JP8") (pin "3") (pinfunction "3_3") (pintype "passive"))
      (node (ref "JP8") (pin "4") (pinfunction "4_4") (pintype "passive"))
      (node (ref "PORTA") (pin "6") (pinfunction "6_6") (pintype "passive"))
      (node (ref "PORTB") (pin "6") (pinfunction "6_6") (pintype "passive"))
      (node (ref "PORTC") (pin "6") (pinfunction "6_6") (pintype "passive"))
      (node (ref "R19") (pin "2") (pinfunction "2_2") (pintype "passive"))
      (node (ref "R20") (pin "2") (pinfunction "2_2") (pintype "passive"))
      (node (ref "R21") (pin "2") (pinfunction "2_2") (pintype "passive"))
      (node (ref "R22") (pin "1") (pinfunction "1_1") (pintype "passive"))
      (node (ref "R23") (pin "1") (pinfunction "1_1") (pintype "passive"))
      (node (ref "R24") (pin "1") (pinfunction "1_1") (pintype "passive"))
      (node (ref "R25") (pin "1") (pinfunction "1_1") (pintype "passive"))
      (node (ref "R26") (pin "1") (pinfunction "1_1") (pintype "passive"))
      (node (ref "R27") (pin "1") (pinfunction "1_1") (pintype "passive"))
      (node (ref "R62") (pin "1") (pinfunction "1_1") (pintype "passive"))
      (node (ref "R63") (pin "1") (pinfunction "1_1") (pintype "passive"))
      (node (ref "R64") (pin "1") (pinfunction "1_1") (pintype "passive"))
      (node (ref "R65") (pin "1") (pinfunction "1_1") (pintype "passive"))
      (node (ref "R66") (pin "1") (pinfunction "1_1") (pintype "passive"))
      (node (ref "R67") (pin "1") (pinfunction "1_1") (pintype "passive"))
      (node (ref "SJ1") (pin "P$2") (pinfunction "2_P$2") (pintype "passive"))
      (node (ref "SJ10") (pin "P$2") (pinfunction "2_P$2") (pintype "passive"))
      (node (ref "SJ4") (pin "P$2") (pinfunction "2_P$2") (pintype "passive"))
      (node (ref "SJ7") (pin "P$2") (pinfunction "2_P$2") (pintype "passive"))
      (node (ref "U$1") (pin "5V2") (pinfunction "5V2_5V2") (pintype "power_in"))
      (node (ref "U11") (pin "10") (pinfunction "SCL_10") (pintype "input"))
      (node (ref "U11") (pin "16") (pinfunction "VCC_16") (pintype "power_in"))
      (node (ref "U13") (pin "10") (pinfunction "SCL_10") (pintype "input"))
      (node (ref "U13") (pin "16") (pinfunction "VCC_16") (pintype "power_in"))
      (node (ref "U7") (pin "3") (pinfunction "VCC_3") (pintype "power_in"))
      (node (ref "U7B") (pin "3") (pinfunction "VDD_3") (pintype "power_in"))
      (node (ref "X6") (pin "1") (pinfunction "1_1") (pintype "passive"))
    )
    (net (code "3") (name "+12V") (class "Default")
      (node (ref "C10") (pin "1") (pinfunction "1_1") (pintype "passive"))
      (node (ref "C6") (pin "1") (pinfunction "1_1") (pintype "passive"))
      (node (ref "C7") (pin "1") (pinfunction "1_1") (pintype "passive"))
      (node (ref "J3") (pin "1") (pinfunction "1_1") (pintype "passive"))
      (node (ref "JP3") (pin "3") (pinfunction "3_3") (pintype "passive"))
      (node (ref "JP4") (pin "2") (pinfunction "2_2") (pintype "passive"))
      (node (ref "SJ11") (pin "P$2") (pinfunction "2_P$2") (pintype "passive"))
      (node (ref "SJ14") (pin "P$2") (pinfunction "2_P$2") (pintype "passive"))
      (node (ref "SJ2") (pin "P$2") (pinfunction "2_P$2") (pintype "passive"))
      (node (ref "SJ5") (pin "P$2") (pinfunction "2_P$2") (pintype "passive"))
      (node (ref "SJ8") (pin "P$2") (pinfunction "2_P$2") (pintype "passive"))
      (node (ref "U10") (pin "4") (pinfunction "V+_4") (pintype "power_in"))
      (node (ref "U3") (pin "6") (pinfunction "VDD_6") (pintype "power_in"))
      (node (ref "U4") (pin "6") (pinfunction "VDD_6") (pintype "power_in"))
      (node (ref "U5") (pin "6") (pinfunction "VDD_6") (pintype "power_in"))
      (node (ref "U6") (pin "6") (pinfunction "VDD_6") (pintype "power_in"))
      (node (ref "U8") (pin "1") (pinfunction "VIN_1") (pintype "bidirectional"))
      (node (ref "U8B") (pin "5") (pinfunction "IN_5") (pintype "input"))
      (node (ref "U9") (pin "4") (pinfunction "V+_4") (pintype "power_in"))
    )
    (net (code "4") (name "/AGND") (class "Default")
      (node (ref "U$1") (pin "AGND") (pinfunction "AGND_AGND") (pintype "power_in"))
    )
    (net (code "5") (name "/AVDD") (class "Default")
      (node (ref "U$1") (pin "AVDD") (pinfunction "AVDD_AVDD") (pintype "power_in"))
    )
    (net (code "6") (name "/CANH") (class "Default")
      (node (ref "J1") (pin "1") (pinfunction "1_1") (pintype "passive"))
      (node (ref "J2") (pin "1") (pinfunction "1_1") (pintype "passive"))
      (node (ref "U7") (pin "7") (pinfunction "CANH_7") (pintype "bidirectional"))
      (node (ref "U7B") (pin "7") (pinfunction "CANH_7") (pintype "bidirectional"))
    )
    (net (code "7") (name "/CANL") (class "Default")
      (node (ref "J1") (pin "2") (pinfunction "2_2") (pintype "passive"))
      (node (ref "J2") (pin "2") (pinfunction "2_2") (pintype "passive"))
      (node (ref "U7") (pin "6") (pinfunction "CANL_6") (pintype "bidirectional"))
      (node (ref "U7B") (pin "6") (pinfunction "CANL_6") (pintype "bidirectional"))
    )
    (net (code "8") (name "/GND4") (class "Default")
      (node (ref "U$1") (pin "GND4") (pinfunction "GND4_GND4") (pintype "power_in"))
    )
    (net (code "9") (name "/PWR_POS") (class "Default")
      (node (ref "J1") (pin "8") (pinfunction "8_8") (pintype "passive"))
      (node (ref "J2") (pin "8") (pinfunction "8_8") (pintype "passive"))
      (node (ref "R40") (pin "1") (pinfunction "1_1") (pintype "passive"))
    )
    (net (code "10") (name "/U5V") (class "Default")
      (node (ref "U$1") (pin "U5V") (pinfunction "U5V_U5V") (pintype "power_in"))
    )
    (net (code "11") (name "/VBAT") (class "Default")
      (node (ref "U$1") (pin "VBAT") (pinfunction "VBAT_VBAT") (pintype "power_in"))
    )
    (net (code "12") (name "/VDD") (class "Default")
      (node (ref "U$1") (pin "VDD") (pinfunction "VDD_VDD") (pintype "power_in"))
    )
    (net (code "13") (name "CANRX") (class "Default")
      (node (ref "U$1") (pin "PB8") (pinfunction "PB8_PB8") (pintype "bidirectional"))
      (node (ref "U7") (pin "4") (pinfunction "RXD_4") (pintype "output"))
      (node (ref "U7B") (pin "4") (pinfunction "RXD_4") (pintype "bidirectional"))
    )
    (net (code "14") (name "CANTX") (class "Default")
      (node (ref "U$1") (pin "PB9") (pinfunction "PB9_PB9") (pintype "bidirectional"))
      (node (ref "U7") (pin "1") (pinfunction "TXD_1") (pintype "input"))
      (node (ref "U7B") (pin "1") (pinfunction "TXD_1") (pintype "bidirectional"))
    )
    (net (code "15") (name "E_CS") (class "Default")
      (node (ref "JP2") (pin "4") (pinfunction "4_4") (pintype "passive"))
      (node (ref "R23") (pin "2") (pinfunction "2_2") (pintype "passive"))
      (node (ref "U$1") (pin "PC10") (pinfunction "PC10_PC10") (pintype "bidirectional"))
    )
    (net (code "16") (name "E_LAT") (class "Default")
      (node (ref "JP3") (pin "1") (pinfunction "1_1") (pintype "passive"))
      (node (ref "R22") (pin "2") (pinfunction "2_2") (pintype "passive"))
      (node (ref "U$1") (pin "PC11") (pinfunction "PC11_PC11") (pintype "bidirectional"))
    )
    (net (code "17") (name "GND") (class "Default")
      (node (ref "C1") (pin "2") (pinfunction "2_2") (pintype "passive"))
      (node (ref "C10") (pin "2") (pinfunction "2_2") (pintype "passive"))
      (node (ref "C11") (pin "2") (pinfunction "2_2") (pintype "passive"))
      (node (ref "C2") (pin "-") (pinfunction "-_-") (pintype "passive"))
      (node (ref "C3") (pin "2") (pinfunction "2_2") (pintype "passive"))
      (node (ref "C4") (pin "2") (pinfunction "2_2") (pintype "passive"))
      (node (ref "C5") (pin "2") (pinfunction "2_2") (pintype "passive"))
      (node (ref "C6") (pin "2") (pinfunction "2_2") (pintype "passive"))
      (node (ref "C7") (pin "2") (pinfunction "2_2") (pintype "passive"))
      (node (ref "C8") (pin "2") (pinfunction "2_2") (pintype "passive"))
      (node (ref "C9") (pin "2") (pinfunction "2_2") (pintype "passive"))
      (node (ref "D1") (pin "A") (pinfunction "A_A") (pintype "passive"))
      (node (ref "J1") (pin "3") (pinfunction "3_3") (pintype "passive"))
      (node (ref "J1") (pin "6") (pinfunction "6_6") (pintype "passive"))
      (node (ref "J1") (pin "7") (pinfunction "7_7") (pintype "passive"))
      (node (ref "J2") (pin "3") (pinfunction "3_3") (pintype "passive"))
      (node (ref "J2") (pin "6") (pinfunction "6_6") (pintype "passive"))
      (node (ref "J2") (pin "7") (pinfunction "7_7") (pintype "passive"))
      (node (ref "J3") (pin "2") (pinfunction "2_2") (pintype "passive"))
      (node (ref "J3") (pin "3") (pinfunction "3_3") (pintype "passive"))
      (node (ref "JP1") (pin "4") (pinfunction "4_4") (pintype "passive"))
      (node (ref "JP3") (pin "4") (pinfunction "4_4") (pintype "passive"))
      (node (ref "JP5") (pin "5") (pinfunction "5_5") (pintype "passive"))
      (node (ref "JP5") (pin "6") (pinfunction "6_6") (pintype "passive"))
      (node (ref "JP6") (pin "5") (pinfunction "5_5") (pintype "passive"))
      (node (ref "JP6") (pin "6") (pinfunction "6_6") (pintype "passive"))
      (node (ref "JP7") (pin "5") (pinfunction "5_5") (pintype "passive"))
      (node (ref "JP7") (pin "6") (pinfunction "6_6") (pintype "passive"))
      (node (ref "JP8") (pin "5") (pinfunction "5_5") (pintype "passive"))
      (node (ref "JP8") (pin "6") (pinfunction "6_6") (pintype "passive"))
      (node (ref "PORTA") (pin "5") (pinfunction "5_5") (pintype "passive"))
      (node (ref "PORTB") (pin "5") (pinfunction "5_5") (pintype "passive"))
      (node (ref "PORTC") (pin "5") (pinfunction "5_5") (pintype "passive"))
      (node (ref "Q1") (pin "2") (pinfunction "S_2") (pintype "passive"))
      (node (ref "Q10") (pin "2") (pinfunction "S_2") (pintype "passive"))
      (node (ref "Q11") (pin "2") (pinfunction "S_2") (pintype "passive"))
      (node (ref "Q12") (pin "2") (pinfunction "S_2") (pintype "passive"))
      (node (ref "Q13") (pin "2") (pinfunction "S_2") (pintype "passive"))
      (node (ref "Q14") (pin "2") (pinfunction "S_2") (pintype "passive"))
      (node (ref "Q15") (pin "2") (pinfunction "S_2") (pintype "passive"))
      (node (ref "Q16") (pin "2") (pinfunction "S_2") (pintype "passive"))
      (node (ref "Q2") (pin "2") (pinfunction "S_2") (pintype "passive"))
      (node (ref "Q3") (pin "2") (pinfunction "S_2") (pintype "passive"))
      (node (ref "Q4") (pin "2") (pinfunction "S_2") (pintype "passive"))
      (node (ref "Q5") (pin "2") (pinfunction "S_2") (pintype "passive"))
      (node (ref "Q6") (pin "2") (pinfunction "S_2") (pintype "passive"))
      (node (ref "Q7") (pin "2") (pinfunction "S_2") (pintype "passive"))
      (node (ref "Q8") (pin "2") (pinfunction "S_2") (pintype "passive"))
      (node (ref "Q9") (pin "2") (pinfunction "S_2") (pintype "passive"))
      (node (ref "R2") (pin "1") (pinfunction "1_1") (pintype "passive"))
      (node (ref "R61") (pin "2") (pinfunction "2_2") (pintype "passive"))
      (node (ref "SJ12") (pin "P$2") (pinfunction "2_P$2") (pintype "passive"))
      (node (ref "SJ3") (pin "2") (pinfunction "2_2") (pintype "passive"))
      (node (ref "SJ6") (pin "P$2") (pinfunction "2_P$2") (pintype "passive"))
      (node (ref "SJ9") (pin "2") (pinfunction "2_2") (pintype "passive"))
      (node (ref "U$1") (pin "GND3") (pinfunction "GND3_GND3") (pintype "power_in"))
      (node (ref "U$1") (pin "GND5") (pinfunction "GND5_GND5") (pintype "power_in"))
      (node (ref "U$1") (pin "GND6") (pinfunction "GND6_GND6") (pintype "power_in"))
      (node (ref "U$1") (pin "GND7") (pinfunction "GND7_GND7") (pintype "power_in"))
      (node (ref "U$1") (pin "GND8") (pinfunction "GND8_GND8") (pintype "power_in"))
      (node (ref "U1") (pin "6") (pinfunction "INH_6") (pintype "input"))
      (node (ref "U1") (pin "8") (pinfunction "GND_8") (pintype "power_in"))
      (node (ref "U10") (pin "11") (pinfunction "V-_11") (pintype "power_in"))
      (node (ref "U11") (pin "13") (pinfunction "G_13") (pintype "input"))
      (node (ref "U11") (pin "8") (pinfunction "GND_8") (pintype "power_in"))
      (node (ref "U13") (pin "13") (pinfunction "G_13") (pintype "input"))
      (node (ref "U13") (pin "8") (pinfunction "GND_8") (pintype "power_in"))
      (node (ref "U2") (pin "6") (pinfunction "INH_6") (pintype "input"))
      (node (ref "U2") (pin "8") (pinfunction "GND_8") (pintype "power_in"))
      (node (ref "U3") (pin "3") (pinfunction "VSS_3") (pintype "power_in"))
      (node (ref "U4") (pin "3") (pinfunction "VSS_3") (pintype "power_in"))
      (node (ref "U5") (pin "3") (pinfunction "VSS_3") (pintype "power_in"))
      (node (ref "U6") (pin "3") (pinfunction "VSS_3") (pintype "power_in"))
      (node (ref "U7") (pin "2") (pinfunction "GND_2") (pintype "power_in"))
      (node (ref "U7B") (pin "2") (pinfunction "VSS_2") (pintype "power_in"))
      (node (ref "U8") (pin "4") (pinfunction "SD_4") (pintype "bidirectional"))
      (node (ref "U8") (pin "5") (pinfunction "GND1_5") (pintype "power_in"))
      (node (ref "U8") (pin "6") (pinfunction "GND2_6") (pintype "power_in"))
      (node (ref "U8") (pin "7") (pinfunction "GND3_7") (pintype "power_in"))
      (node (ref "U8") (pin "8") (pinfunction "GND4_8") (pintype "power_in"))
      (node (ref "U8B") (pin "2") (pinfunction "GNDSIG_2") (pintype "input"))
      (node (ref "U8B") (pin "3") (pinfunction "~{ON/OFF}_3") (pintype "input"))
      (node (ref "U8B") (pin "4") (pinfunction "GND_4") (pintype "power_in"))
      (node (ref "U9") (pin "11") (pinfunction "V-_11") (pintype "power_in"))
      (node (ref "X6") (pin "2") (pinfunction "2_2") (pintype "passive"))
    )
    (net (code "18") (name "I2CSCL") (class "Default")
      (node (ref "JP1") (pin "2") (pinfunction "2_2") (pintype "passive"))
      (node (ref "R63") (pin "2") (pinfunction "2_2") (pintype "passive"))
      (node (ref "U$1") (pin "PB6") (pinfunction "PB6_PB6") (pintype "bidirectional"))
    )
    (net (code "19") (name "I2CSDA") (class "Default")
      (node (ref "JP1") (pin "1") (pinfunction "1_1") (pintype "passive"))
      (node (ref "R62") (pin "2") (pinfunction "2_2") (pintype "passive"))
      (node (ref "U$1") (pin "PB7") (pinfunction "PB7_PB7") (pintype "bidirectional"))
    )
    (net (code "20") (name "ILAT") (class "Default")
      (node (ref "U$1") (pin "PA6") (pinfunction "PA6_PA6") (pintype "bidirectional"))
      (node (ref "U1") (pin "15") (pinfunction "SH/~{LD}_15") (pintype "input"))
      (node (ref "U2") (pin "15") (pinfunction "SH/~{LD}_15") (pintype "input"))
    )
    (net (code "21") (name "MISO") (class "Default")
      (node (ref "JP2") (pin "1") (pinfunction "1_1") (pintype "passive"))
      (node (ref "U$1") (pin "PB4") (pinfunction "PB4_PB4") (pintype "bidirectional"))
    )
    (net (code "22") (name "MISO2") (class "Default")
      (node (ref "SJ13") (pin "P$2") (pinfunction "2_P$2") (pintype "passive"))
      (node (ref "U$1") (pin "PC2") (pinfunction "PC2_PC2") (pintype "bidirectional"))
      (node (ref "U2") (pin "13") (pinfunction "QH_13") (pintype "output"))
    )
    (net (code "23") (name "MOSI") (class "Default")
      (node (ref "R20") (pin "1") (pinfunction "1_1") (pintype "passive"))
      (node (ref "SJ15") (pin "1") (pinfunction "1_1") (pintype "passive"))
      (node (ref "SJ17") (pin "P$2") (pinfunction "2_P$2") (pintype "passive"))
      (node (ref "U$1") (pin "PB5") (pinfunction "PB5_PB5") (pintype "bidirectional"))
      (node (ref "U11") (pin "14") (pinfunction "SER_14") (pintype "input"))
    )
    (net (code "24") (name "Net-(D2-PadA)") (class "Default")
      (node (ref "D2") (pin "A") (pinfunction "A_A") (pintype "passive"))
      (node (ref "JP4") (pin "4") (pinfunction "4_4") (pintype "passive"))
    )
    (net (code "25") (name "Net-(D2-PadC)") (class "Default")
      (node (ref "D2") (pin "C") (pinfunction "C_C") (pintype "passive"))
      (node (ref "JP4") (pin "1") (pinfunction "1_1") (pintype "passive"))
    )
    (net (code "26") (name "Net-(J1-Pad4)") (class "Default")
      (node (ref "J1") (pin "4") (pinfunction "4_4") (pintype "passive"))
      (node (ref "J2") (pin "4") (pinfunction "4_4") (pintype "passive"))
    )
    (net (code "27") (name "Net-(J1-Pad5)") (class "Default")
      (node (ref "J1") (pin "5") (pinfunction "5_5") (pintype "passive"))
      (node (ref "J2") (pin "5") (pinfunction "5_5") (pintype "passive"))
    )
    (net (code "28") (name "Net-(JP4-Pad3)") (class "Default")
      (node (ref "JP4") (pin "3") (pinfunction "3_3") (pintype "passive"))
      (node (ref "R40") (pin "2") (pinfunction "2_2") (pintype "passive"))
    )
    (net (code "29") (name "Net-(PORTA-Pad1)") (class "Default")
      (node (ref "PORTA") (pin "1") (pinfunction "1_1") (pintype "passive"))
      (node (ref "R44") (pin "2") (pinfunction "2_2") (pintype "passive"))
      (node (ref "R53") (pin "2") (pinfunction "2_2") (pintype "passive"))
      (node (ref "RN3") (pin "1") (pinfunction "1_1") (pintype "passive"))
      (node (ref "RN4") (pin "9") (pinfunction "9_9") (pintype "passive"))
      (node (ref "X1") (pin "1") (pinfunction "1_1") (pintype "passive"))
    )
    (net (code "30") (name "Net-(PORTB-Pad1)") (class "Default")
      (node (ref "PORTB") (pin "1") (pinfunction "1_1") (pintype "passive"))
      (node (ref "R35") (pin "2") (pinfunction "2_2") (pintype "passive"))
      (node (ref "R45") (pin "2") (pinfunction "2_2") (pintype "passive"))
      (node (ref "RN1") (pin "1") (pinfunction "1_1") (pintype "passive"))
      (node (ref "RN2") (pin "9") (pinfunction "9_9") (pintype "passive"))
      (node (ref "X2") (pin "1") (pinfunction "1_1") (pintype "passive"))
    )
    (net (code "31") (name "Net-(Q1-D)") (class "Default")
      (node (ref "Q1") (pin "3") (pinfunction "D_3") (pintype "passive"))
      (node (ref "U12") (pin "18") (pinfunction "O1_18") (pintype "open_collector"))
      (node (ref "X5") (pin "1") (pinfunction "1_1") (pintype "passive"))
    )
    (net (code "32") (name "Net-(Q1-G)") (class "Default")
      (node (ref "Q1") (pin "1") (pinfunction "G_1") (pintype "passive"))
      (node (ref "R3") (pin "2") (pinfunction "2_2") (pintype "passive"))
    )
    (net (code "33") (name "Net-(Q2-D)") (class "Default")
      (node (ref "Q2") (pin "3") (pinfunction "D_3") (pintype "passive"))
      (node (ref "U12") (pin "17") (pinfunction "O2_17") (pintype "open_collector"))
      (node (ref "X5") (pin "2") (pinfunction "2_2") (pintype "passive"))
    )
    (net (code "34") (name "Net-(Q2-G)") (class "Default")
      (node (ref "Q2") (pin "1") (pinfunction "G_1") (pintype "passive"))
      (node (ref "R4") (pin "2") (pinfunction "2_2") (pintype "passive"))
    )
    (net (code "35") (name "Net-(Q3-D)") (class "Default")
      (node (ref "Q3") (pin "3") (pinfunction "D_3") (pintype "passive"))
      (node (ref "U12") (pin "16") (pinfunction "O3_16") (pintype "open_collector"))
      (node (ref "X5") (pin "3") (pinfunction "3_3") (pintype "passive"))
    )
    (net (code "36") (name "Net-(Q3-G)") (class "Default")
      (node (ref "Q3") (pin "1") (pinfunction "G_1") (pintype "passive"))
      (node (ref "R5") (pin "2") (pinfunction "2_2") (pintype "passive"))
    )
    (net (code "37") (name "Net-(Q4-D)") (class "Default")
      (node (ref "Q4") (pin "3") (pinfunction "D_3") (pintype "passive"))
      (node (ref "U12") (pin "15") (pinfunction "O4_15") (pintype "open_collector"))
      (node (ref "X5") (pin "4") (pinfunction "4_4") (pintype "passive"))
    )
    (net (code "38") (name "Net-(Q4-G)") (class "Default")
      (node (ref "Q4") (pin "1") (pinfunction "G_1") (pintype "passive"))
      (node (ref "R6") (pin "2") (pinfunction "2_2") (pintype "passive"))
    )
    (net (code "39") (name "Net-(Q5-D)") (class "Default")
      (node (ref "Q5") (pin "3") (pinfunction "D_3") (pintype "passive"))
      (node (ref "U12") (pin "14") (pinfunction "O5_14") (pintype "open_collector"))
      (node (ref "X5") (pin "5") (pinfunction "5_5") (pintype "passive"))
    )
    (net (code "40") (name "Net-(Q5-G)") (class "Default")
      (node (ref "Q5") (pin "1") (pinfunction "G_1") (pintype "passive"))
      (node (ref "R7") (pin "2") (pinfunction "2_2") (pintype "passive"))
    )
    (net (code "41") (name "Net-(Q6-D)") (class "Default")
      (node (ref "Q6") (pin "3") (pinfunction "D_3") (pintype "passive"))
      (node (ref "U12") (pin "13") (pinfunction "O6_13") (pintype "open_collector"))
      (node (ref "X5") (pin "6") (pinfunction "6_6") (pintype "passive"))
    )
    (net (code "42") (name "Net-(Q6-G)") (class "Default")
      (node (ref "Q6") (pin "1") (pinfunction "G_1") (pintype "passive"))
      (node (ref "R8") (pin "2") (pinfunction "2_2") (pintype "passive"))
    )
    (net (code "43") (name "Net-(Q7-D)") (class "Default")
      (node (ref "Q7") (pin "3") (pinfunction "D_3") (pintype "passive"))
      (node (ref "U12") (pin "12") (pinfunction "O7_12") (pintype "open_collector"))
      (node (ref "X5") (pin "7") (pinfunction "7_7") (pintype "passive"))
    )
    (net (code "44") (name "Net-(Q7-G)") (class "Default")
      (node (ref "Q7") (pin "1") (pinfunction "G_1") (pintype "passive"))
      (node (ref "R9") (pin "2") (pinfunction "2_2") (pintype "passive"))
    )
    (net (code "45") (name "Net-(Q8-D)") (class "Default")
      (node (ref "Q8") (pin "3") (pinfunction "D_3") (pintype "passive"))
      (node (ref "U12") (pin "11") (pinfunction "O8_11") (pintype "open_collector"))
      (node (ref "X5") (pin "8") (pinfunction "8_8") (pintype "passive"))
    )
    (net (code "46") (name "Net-(Q8-G)") (class "Default")
      (node (ref "Q8") (pin "1") (pinfunction "G_1") (pintype "passive"))
      (node (ref "R10") (pin "2") (pinfunction "2_2") (pintype "passive"))
    )
    (net (code "47") (name "Net-(Q9-D)") (class "Default")
      (node (ref "Q9") (pin "3") (pinfunction "D_3") (pintype "passive"))
      (node (ref "U14") (pin "18") (pinfunction "O1_18") (pintype "open_collector"))
      (node (ref "X4") (pin "1") (pinfunction "1_1") (pintype "passive"))
    )
    (net (code "48") (name "Net-(Q9-G)") (class "Default")
      (node (ref "Q9") (pin "1") (pinfunction "G_1") (pintype "passive"))
      (node (ref "R11") (pin "2") (pinfunction "2_2") (pintype "passive"))
    )
    (net (code "49") (name "Net-(Q10-D)") (class "Default")
      (node (ref "Q10") (pin "3") (pinfunction "D_3") (pintype "passive"))
      (node (ref "U14") (pin "17") (pinfunction "O2_17") (pintype "open_collector"))
      (node (ref "X4") (pin "2") (pinfunction "2_2") (pintype "passive"))
    )
    (net (code "50") (name "Net-(Q10-G)") (class "Default")
      (node (ref "Q10") (pin "1") (pinfunction "G_1") (pintype "passive"))
      (node (ref "R12") (pin "2") (pinfunction "2_2") (pintype "passive"))
    )
    (net (code "51") (name "Net-(Q11-D)") (class "Default")
      (node (ref "Q11") (pin "3") (pinfunction "D_3") (pintype "passive"))
      (node (ref "U14") (pin "16") (pinfunction "O3_16") (pintype "open_collector"))
      (node (ref "X4") (pin "3") (pinfunction "3_3") (pintype "passive"))
    )
    (net (code "52") (name "Net-(Q11-G)") (class "Default")
      (node (ref "Q11") (pin "1") (pinfunction "G_1") (pintype "passive"))
      (node (ref "R13") (pin "2") (pinfunction "2_2") (pintype "passive"))
    )
    (net (code "53") (name "Net-(Q12-D)") (class "Default")
      (node (ref "Q12") (pin "3") (pinfunction "D_3") (pintype "passive"))
      (node (ref "U14") (pin "15") (pinfunction "O4_15") (pintype "open_collector"))
      (node (ref "X4") (pin "4") (pinfunction "4_4") (pintype "passive"))
    )
    (net (code "54") (name "Net-(Q12-G)") (class "Default")
      (node (ref "Q12") (pin "1") (pinfunction "G_1") (pintype "passive"))
      (node (ref "R14") (pin "2") (pinfunction "2_2") (pintype "passive"))
    )
    (net (code "55") (name "Net-(Q13-D)") (class "Default")
      (node (ref "Q13") (pin "3") (pinfunction "D_3") (pintype "passive"))
      (node (ref "U14") (pin "14") (pinfunction "O5_14") (pintype "open_collector"))
      (node (ref "X4") (pin "5") (pinfunction "5_5") (pintype "passive"))
    )
    (net (code "56") (name "Net-(Q13-G)") (class "Default")
      (node (ref "Q13") (pin "1") (pinfunction "G_1") (pintype "passive"))
      (node (ref "R15") (pin "2") (pinfunction "2_2") (pintype "passive"))
    )
    (net (code "57") (name "Net-(Q14-D)") (class "Default")
      (node (ref "Q14") (pin "3") (pinfunction "D_3") (pintype "passive"))
      (node (ref "U14") (pin "13") (pinfunction "O6_13") (pintype "open_collector"))
      (node (ref "X4") (pin "6") (pinfunction "6_6") (pintype "passive"))
    )
    (net (code "58") (name "Net-(Q14-G)") (class "Default")
      (node (ref "Q14") (pin "1") (pinfunction "G_1") (pintype "passive"))
      (node (ref "R16") (pin "2") (pinfunction "2_2") (pintype "passive"))
    )
    (net (code "59") (name "Net-(Q15-D)") (class "Default")
      (node (ref "Q15") (pin "3") (pinfunction "D_3") (pintype "passive"))
      (node (ref "U14") (pin "12") (pinfunction "O7_12") (pintype "open_collector"))
      (node (ref "X4") (pin "7") (pinfunction "7_7") (pintype "passive"))
    )
    (net (code "60") (name "Net-(Q15-G)") (class "Default")
      (node (ref "Q15") (pin "1") (pinfunction "G_1") (pintype "passive"))
      (node (ref "R17") (pin "2") (pinfunction "2_2") (pintype "passive"))
    )
    (net (code "61") (name "Net-(Q16-D)") (class "Default")
      (node (ref "Q16") (pin "3") (pinfunction "D_3") (pintype "passive"))
      (node (ref "U14") (pin "11") (pinfunction "O8_11") (pintype "open_collector"))
      (node (ref "X4") (pin "8") (pinfunction "8_8") (pintype "passive"))
    )
    (net (code "62") (name "Net-(Q16-G)") (class "Default")
      (node (ref "Q16") (pin "1") (pinfunction "G_1") (pintype "passive"))
      (node (ref "R18") (pin "2") (pinfunction "2_2") (pintype "passive"))
    )
    (net (code "63") (name "Net-(RN1A-2)") (class "Default")
      (node (ref "R35") (pin "1") (pinfunction "1_1") (pintype "passive"))
      (node (ref "RN1") (pin "16") (pinfunction "2_16") (pintype "passive"))
      (node (ref "U2") (pin "14") (pinfunction "H_14") (pintype "input"))
    )
    (net (code "64") (name "Net-(RN1B-1)") (class "Default")
      (node (ref "PORTB") (pin "2") (pinfunction "2_2") (pintype "passive"))
      (node (ref "R34") (pin "2") (pinfunction "2_2") (pintype "passive"))
      (node (ref "R46") (pin "1") (pinfunction "1_1") (pintype "passive"))
      (node (ref "RN1") (pin "2") (pinfunction "1_2") (pintype "passive"))
      (node (ref "RN2") (pin "8") (pinfunction "8_8") (pintype "passive"))
      (node (ref "X2") (pin "2") (pinfunction "2_2") (pintype "passive"))
    )
    (net (code "65") (name "Net-(RN1B-2)") (class "Default")
      (node (ref "R34") (pin "1") (pinfunction "1_1") (pintype "passive"))
      (node (ref "RN1") (pin "15") (pinfunction "2_15") (pintype "passive"))
      (node (ref "U2") (pin "12") (pinfunction "G_12") (pintype "input"))
    )
    (net (code "66") (name "Net-(RN1C-1)") (class "Default")
      (node (ref "PORTB") (pin "3") (pinfunction "3_3") (pintype "passive"))
      (node (ref "R33") (pin "2") (pinfunction "2_2") (pintype "passive"))
      (node (ref "R47") (pin "1") (pinfunction "1_1") (pintype "passive"))
      (node (ref "RN1") (pin "3") (pinfunction "1_3") (pintype "passive"))
      (node (ref "RN2") (pin "7") (pinfunction "7_7") (pintype "passive"))
      (node (ref "X2") (pin "3") (pinfunction "3_3") (pintype "passive"))
    )
    (net (code "67") (name "Net-(RN1C-2)") (class "Default")
      (node (ref "R33") (pin "1") (pinfunction "1_1") (pintype "passive"))
      (node (ref "RN1") (pin "14") (pinfunction "2_14") (pintype "passive"))
      (node (ref "U2") (pin "11") (pinfunction "F_11") (pintype "input"))
    )
    (net (code "68") (name "Net-(RN1D-1)") (class "Default")
      (node (ref "PORTB") (pin "4") (pinfunction "4_4") (pintype "passive"))
      (node (ref "R32") (pin "2") (pinfunction "2_2") (pintype "passive"))
      (node (ref "R48") (pin "1") (pinfunction "1_1") (pintype "passive"))
      (node (ref "RN1") (pin "4") (pinfunction "1_4") (pintype "passive"))
      (node (ref "RN2") (pin "6") (pinfunction "6_6") (pintype "passive"))
      (node (ref "X2") (pin "4") (pinfunction "4_4") (pintype "passive"))
    )
    (net (code "69") (name "Net-(RN1D-2)") (class "Default")
      (node (ref "R32") (pin "1") (pinfunction "1_1") (pintype "passive"))
      (node (ref "RN1") (pin "13") (pinfunction "2_13") (pintype "passive"))
      (node (ref "U2") (pin "10") (pinfunction "E_10") (pintype "input"))
    )
    (net (code "70") (name "Net-(RN1E-1)") (class "Default")
      (node (ref "PORTB") (pin "7") (pinfunction "7_7") (pintype "passive"))
      (node (ref "R31") (pin "2") (pinfunction "2_2") (pintype "passive"))
      (node (ref "R49") (pin "1") (pinfunction "1_1") (pintype "passive"))
      (node (ref "RN1") (pin "5") (pinfunction "1_5") (pintype "passive"))
      (node (ref "RN2") (pin "5") (pinfunction "5_5") (pintype "passive"))
      (node (ref "X2") (pin "5") (pinfunction "5_5") (pintype "passive"))
    )
    (net (code "71") (name "Net-(RN1E-2)") (class "Default")
      (node (ref "R31") (pin "1") (pinfunction "1_1") (pintype "passive"))
      (node (ref "RN1") (pin "12") (pinfunction "2_12") (pintype "passive"))
      (node (ref "U2") (pin "5") (pinfunction "D_5") (pintype "input"))
    )
    (net (code "72") (name "Net-(RN1F-1)") (class "Default")
      (node (ref "PORTB") (pin "8") (pinfunction "8_8") (pintype "passive"))
      (node (ref "R30") (pin "2") (pinfunction "2_2") (pintype "passive"))
      (node (ref "R50") (pin "1") (pinfunction "1_1") (pintype "passive"))
      (node (ref "RN1") (pin "6") (pinfunction "1_6") (pintype "passive"))
      (node (ref "RN2") (pin "4") (pinfunction "4_4") (pintype "passive"))
      (node (ref "X2") (pin "6") (pinfunction "6_6") (pintype "passive"))
    )
    (net (code "73") (name "Net-(RN1F-2)") (class "Default")
      (node (ref "R30") (pin "1") (pinfunction "1_1") (pintype "passive"))
      (node (ref "RN1") (pin "11") (pinfunction "2_11") (pintype "passive"))
      (node (ref "U2") (pin "4") (pinfunction "C_4") (pintype "input"))
    )
    (net (code "74") (name "Net-(RN1G-1)") (class "Default")
      (node (ref "PORTB") (pin "9") (pinfunction "9_9") (pintype "passive"))
      (node (ref "R29") (pin "2") (pinfunction "2_2") (pintype "passive"))
      (node (ref "R51") (pin "1") (pinfunction "1_1") (pintype "passive"))
      (node (ref "RN1") (pin "7") (pinfunction "1_7") (pintype "passive"))
      (node (ref "RN2") (pin "3") (pinfunction "3_3") (pintype "passive"))
      (node (ref "X2") (pin "7") (pinfunction "7_7") (pintype "passive"))
    )
    (net (code "75") (name "Net-(RN1G-2)") (class "Default")
      (node (ref "R29") (pin "1") (pinfunction "1_1") (pintype "passive"))
      (node (ref "RN1") (pin "10") (pinfunction "2_10") (pintype "passive"))
      (node (ref "U2") (pin "3") (pinfunction "B_3") (pintype "input"))
    )
    (net (code "76") (name "Net-(RN1H-1)") (class "Default")
      (node (ref "PORTB") (pin "10") (pinfunction "10_10") (pintype "passive"))
      (node (ref "R28") (pin "2") (pinfunction "2_2") (pintype "passive"))
      (node (ref "R52") (pin "1") (pinfunction "1_1") (pintype "passive"))
      (node (ref "RN1") (pin "8") (pinfunction "1_8") (pintype "passive"))
      (node (ref "RN2") (pin "2") (pinfunction "2_2") (pintype "passive"))
      (node (ref "X2") (pin "8") (pinfunction "8_8") (pintype "passive"))
    )
    (net (code "77") (name "Net-(RN1H-2)") (class "Default")
      (node (ref "R28") (pin "1") (pinfunction "1_1") (pintype "passive"))
      (node (ref "RN1") (pin "9") (pinfunction "2_9") (pintype "passive"))
      (node (ref "U2") (pin "2") (pinfunction "A_2") (pintype "input"))
    )
    (net (code "78") (name "Net-(RN3A-2)") (class "Default")
      (node (ref "R44") (pin "1") (pinfunction "1_1") (pintype "passive"))
      (node (ref "RN3") (pin "16") (pinfunction "2_16") (pintype "passive"))
      (node (ref "U1") (pin "14") (pinfunction "H_14") (pintype "input"))
    )
    (net (code "79") (name "Net-(RN3B-1)") (class "Default")
      (node (ref "PORTA") (pin "2") (pinfunction "2_2") (pintype "passive"))
      (node (ref "R43") (pin "2") (pinfunction "2_2") (pintype "passive"))
      (node (ref "R54") (pin "2") (pinfunction "2_2") (pintype "passive"))
      (node (ref "RN3") (pin "2") (pinfunction "1_2") (pintype "passive"))
      (node (ref "RN4") (pin "8") (pinfunction "8_8") (pintype "passive"))
      (node (ref "X1") (pin "2") (pinfunction "2_2") (pintype "passive"))
    )
    (net (code "80") (name "Net-(RN3B-2)") (class "Default")
      (node (ref "R43") (pin "1") (pinfunction "1_1") (pintype "passive"))
      (node (ref "RN3") (pin "15") (pinfunction "2_15") (pintype "passive"))
      (node (ref "U1") (pin "12") (pinfunction "G_12") (pintype "input"))
    )
    (net (code "81") (name "Net-(RN3C-1)") (class "Default")
      (node (ref "PORTA") (pin "3") (pinfunction "3_3") (pintype "passive"))
      (node (ref "R42") (pin "2") (pinfunction "2_2") (pintype "passive"))
      (node (ref "R55") (pin "2") (pinfunction "2_2") (pintype "passive"))
      (node (ref "RN3") (pin "3") (pinfunction "1_3") (pintype "passive"))
      (node (ref "RN4") (pin "7") (pinfunction "7_7") (pintype "passive"))
      (node (ref "X1") (pin "3") (pinfunction "3_3") (pintype "passive"))
    )
    (net (code "82") (name "Net-(RN3C-2)") (class "Default")
      (node (ref "R42") (pin "1") (pinfunction "1_1") (pintype "passive"))
      (node (ref "RN3") (pin "14") (pinfunction "2_14") (pintype "passive"))
      (node (ref "U1") (pin "11") (pinfunction "F_11") (pintype "input"))
    )
    (net (code "83") (name "Net-(RN3D-1)") (class "Default")
      (node (ref "PORTA") (pin "4") (pinfunction "4_4") (pintype "passive"))
      (node (ref "R41") (pin "2") (pinfunction "2_2") (pintype "passive"))
      (node (ref "R56") (pin "2") (pinfunction "2_2") (pintype "passive"))
      (node (ref "RN3") (pin "4") (pinfunction "1_4") (pintype "passive"))
      (node (ref "RN4") (pin "6") (pinfunction "6_6") (pintype "passive"))
      (node (ref "X1") (pin "4") (pinfunction "4_4") (pintype "passive"))
    )
    (net (code "84") (name "Net-(RN3D-2)") (class "Default")
      (node (ref "R41") (pin "1") (pinfunction "1_1") (pintype "passive"))
      (node (ref "RN3") (pin "13") (pinfunction "2_13") (pintype "passive"))
      (node (ref "U1") (pin "10") (pinfunction "E_10") (pintype "input"))
    )
    (net (code "85") (name "Net-(RN3E-1)") (class "Default")
      (node (ref "PORTA") (pin "7") (pinfunction "7_7") (pintype "passive"))
      (node (ref "R39") (pin "2") (pinfunction "2_2") (pintype "passive"))
      (node (ref "R57") (pin "2") (pinfunction "2_2") (pintype "passive"))
      (node (ref "RN3") (pin "5") (pinfunction "1_5") (pintype "passive"))
      (node (ref "RN4") (pin "5") (pinfunction "5_5") (pintype "passive"))
      (node (ref "X1") (pin "5") (pinfunction "5_5") (pintype "passive"))
    )
    (net (code "86") (name "Net-(RN3E-2)") (class "Default")
      (node (ref "R39") (pin "1") (pinfunction "1_1") (pintype "passive"))
      (node (ref "RN3") (pin "12") (pinfunction "2_12") (pintype "passive"))
      (node (ref "U1") (pin "5") (pinfunction "D_5") (pintype "input"))
    )
    (net (code "87") (name "Net-(RN3F-1)") (class "Default")
      (node (ref "PORTA") (pin "8") (pinfunction "8_8") (pintype "passive"))
      (node (ref "R38") (pin "2") (pinfunction "2_2") (pintype "passive"))
      (node (ref "R58") (pin "2") (pinfunction "2_2") (pintype "passive"))
      (node (ref "RN3") (pin "6") (pinfunction "1_6") (pintype "passive"))
      (node (ref "RN4") (pin "4") (pinfunction "4_4") (pintype "passive"))
      (node (ref "X1") (pin "6") (pinfunction "6_6") (pintype "passive"))
    )
    (net (code "88") (name "Net-(RN3F-2)") (class "Default")
      (node (ref "R38") (pin "1") (pinfunction "1_1") (pintype "passive"))
      (node (ref "RN3") (pin "11") (pinfunction "2_11") (pintype "passive"))
      (node (ref "U1") (pin "4") (pinfunction "C_4") (pintype "input"))
    )
    (net (code "89") (name "Net-(RN3G-1)") (class "Default")
      (node (ref "PORTA") (pin "9") (pinfunction "9_9") (pintype "passive"))
      (node (ref "R37") (pin "2") (pinfunction "2_2") (pintype "passive"))
      (node (ref "R59") (pin "2") (pinfunction "2_2") (pintype "passive"))
      (node (ref "RN3") (pin "7") (pinfunction "1_7") (pintype "passive"))
      (node (ref "RN4") (pin "3") (pinfunction "3_3") (pintype "passive"))
      (node (ref "X1") (pin "7") (pinfunction "7_7") (pintype "passive"))
    )
    (net (code "90") (name "Net-(RN3G-2)") (class "Default")
      (node (ref "R37") (pin "1") (pinfunction "1_1") (pintype "passive"))
      (node (ref "RN3") (pin "10") (pinfunction "2_10") (pintype "passive"))
      (node (ref "U1") (pin "3") (pinfunction "B_3") (pintype "input"))
    )
    (net (code "91") (name "Net-(RN3H-1)") (class "Default")
      (node (ref "PORTA") (pin "10") (pinfunction "10_10") (pintype "passive"))
      (node (ref "R36") (pin "2") (pinfunction "2_2") (pintype "passive"))
      (node (ref "R60") (pin "2") (pinfunction "2_2") (pintype "passive"))
      (node (ref "RN3") (pin "8") (pinfunction "1_8") (pintype "passive"))
      (node (ref "RN4") (pin "2") (pinfunction "2_2") (pintype "passive"))
      (node (ref "X1") (pin "8") (pinfunction "8_8") (pintype "passive"))
    )
    (net (code "92") (name "Net-(RN3H-2)") (class "Default")
      (node (ref "R36") (pin "1") (pinfunction "1_1") (pintype "passive"))
      (node (ref "RN3") (pin "9") (pinfunction "2_9") (pintype "passive"))
      (node (ref "U1") (pin "2") (pinfunction "A_2") (pintype "input"))
    )
    (net (code "93") (name "Net-(SJ1-1)") (class "Default")
      (node (ref "SJ1") (pin "P$1") (pinfunction "1_P$1") (pintype "passive"))
      (node (ref "SJ2") (pin "P$1") (pinfunction "1_P$1") (pintype "passive"))
      (node (ref "SJ3") (pin "1") (pinfunction "1_1") (pintype "passive"))
      (node (ref "U12") (pin "9") (pinfunction "GND_9") (pintype "power_in"))
    )
    (net (code "94") (name "Net-(SJ4-1)") (class "Default")
      (node (ref "SJ4") (pin "P$1") (pinfunction "1_P$1") (pintype "passive"))
      (node (ref "SJ5") (pin "P$1") (pinfunction "1_P$1") (pintype "passive"))
      (node (ref "SJ6") (pin "P$1") (pinfunction "1_P$1") (pintype "passive"))
      (node (ref "U12") (pin "10") (pinfunction "CD+_10") (pintype "passive"))
    )
    (net (code "95") (name "Net-(SJ7-1)") (class "Default")
      (node (ref "SJ7") (pin "P$1") (pinfunction "1_P$1") (pintype "passive"))
      (node (ref "SJ8") (pin "P$1") (pinfunction "1_P$1") (pintype "passive"))
      (node (ref "SJ9") (pin "1") (pinfunction "1_1") (pintype "passive"))
      (node (ref "U14") (pin "9") (pinfunction "GND_9") (pintype "power_in"))
    )
    (net (code "96") (name "Net-(SJ10-1)") (class "Default")
      (node (ref "SJ10") (pin "P$1") (pinfunction "1_P$1") (pintype "passive"))
      (node (ref "SJ11") (pin "P$1") (pinfunction "1_P$1") (pintype "passive"))
      (node (ref "SJ12") (pin "P$1") (pinfunction "1_P$1") (pintype "passive"))
      (node (ref "U14") (pin "10") (pinfunction "CD+_10") (pintype "passive"))
    )
    (net (code "97") (name "Net-(SJ13-1)") (class "Default")
      (node (ref "SJ13") (pin "P$1") (pinfunction "1_P$1") (pintype "passive"))
      (node (ref "U$1") (pin "PB14") (pinfunction "PB14_PB14") (pintype "bidirectional"))
    )
    (net (code "98") (name "Net-(SJ14-1)") (class "Default")
      (node (ref "SJ14") (pin "P$1") (pinfunction "1_P$1") (pintype "passive"))
      (node (ref "U$1") (pin "VIN2") (pinfunction "VIN2_VIN2") (pintype "power_in"))
    )
    (net (code "99") (name "Net-(SJ16-2)") (class "Default")
      (node (ref "JP2") (pin "2") (pinfunction "2_2") (pintype "passive"))
      (node (ref "SJ15") (pin "2") (pinfunction "2_2") (pintype "passive"))
      (node (ref "SJ16") (pin "P$2") (pinfunction "2_P$2") (pintype "passive"))
    )
    (net (code "100") (name "Net-(SJ18-2)") (class "Default")
      (node (ref "SJ18") (pin "P$2") (pinfunction "2_P$2") (pintype "passive"))
      (node (ref "U7") (pin "5") (pinfunction "VREF_5") (pintype "output"))
      (node (ref "U7B") (pin "5") (pinfunction "VREF_5") (pintype "bidirectional"))
    )
    (net (code "101") (name "Net-(U3A-O)") (class "Default")
      (node (ref "PORTC") (pin "1") (pinfunction "1_1") (pintype "passive"))
      (node (ref "U3") (pin "7") (pinfunction "O_7") (pintype "output"))
      (node (ref "U9") (pin "7") (pinfunction "OUT_7") (pintype "output"))
      (node (ref "X3") (pin "1") (pinfunction "1_1") (pintype "passive"))
    )
    (net (code "102") (name "Net-(U3B-O)") (class "Default")
      (node (ref "PORTC") (pin "2") (pinfunction "2_2") (pintype "passive"))
      (node (ref "U3") (pin "5") (pinfunction "O_5") (pintype "output"))
      (node (ref "U9") (pin "8") (pinfunction "OUT_8") (pintype "output"))
      (node (ref "X3") (pin "2") (pinfunction "2_2") (pintype "passive"))
    )
    (net (code "103") (name "Net-(U4A-O)") (class "Default")
      (node (ref "PORTC") (pin "4") (pinfunction "4_4") (pintype "passive"))
      (node (ref "U4") (pin "7") (pinfunction "O_7") (pintype "output"))
      (node (ref "U9") (pin "14") (pinfunction "OUT_14") (pintype "output"))
      (node (ref "X3") (pin "4") (pinfunction "4_4") (pintype "passive"))
    )
    (net (code "104") (name "Net-(U4B-O)") (class "Default")
      (node (ref "PORTC") (pin "3") (pinfunction "3_3") (pintype "passive"))
      (node (ref "U4") (pin "5") (pinfunction "O_5") (pintype "output"))
      (node (ref "U9") (pin "1") (pinfunction "OUT_1") (pintype "output"))
      (node (ref "X3") (pin "3") (pinfunction "3_3") (pintype "passive"))
    )
    (net (code "105") (name "Net-(U7-RS)") (class "Default")
      (node (ref "R61") (pin "1") (pinfunction "1_1") (pintype "passive"))
      (node (ref "U7") (pin "8") (pinfunction "RS_8") (pintype "input"))
      (node (ref "U7B") (pin "8") (pinfunction "RS_8") (pintype "bidirectional"))
    )
    (net (code "106") (name "Net-(U8-VOUT)") (class "Default")
      (node (ref "D1") (pin "C") (pinfunction "C_C") (pintype "passive"))
      (node (ref "L1") (pin "2") (pinfunction "2_2") (pintype "passive"))
      (node (ref "U8") (pin "2") (pinfunction "VOUT_2") (pintype "bidirectional"))
      (node (ref "U8B") (pin "7") (pinfunction "OUT_7") (pintype "passive"))
    )
    (net (code "107") (name "Net-(U10A--IN)") (class "Default")
      (node (ref "R1") (pin "1") (pinfunction "1_1") (pintype "passive"))
      (node (ref "R2") (pin "2") (pinfunction "2_2") (pintype "passive"))
      (node (ref "U10") (pin "13") (pinfunction "-IN_13") (pintype "input"))
      (node (ref "U10") (pin "2") (pinfunction "-IN_2") (pintype "input"))
      (node (ref "U10") (pin "6") (pinfunction "-IN_6") (pintype "input"))
      (node (ref "U10") (pin "9") (pinfunction "-IN_9") (pintype "input"))
      (node (ref "U9") (pin "13") (pinfunction "-IN_13") (pintype "input"))
      (node (ref "U9") (pin "2") (pinfunction "-IN_2") (pintype "input"))
      (node (ref "U9") (pin "6") (pinfunction "-IN_6") (pintype "input"))
      (node (ref "U9") (pin "9") (pinfunction "-IN_9") (pintype "input"))
    )
    (net (code "108") (name "Net-(U10A-OUT)") (class "Default")
      (node (ref "PORTC") (pin "9") (pinfunction "9_9") (pintype "passive"))
      (node (ref "U10") (pin "1") (pinfunction "OUT_1") (pintype "output"))
      (node (ref "U6") (pin "5") (pinfunction "O_5") (pintype "output"))
      (node (ref "X3") (pin "7") (pinfunction "7_7") (pintype "passive"))
    )
    (net (code "109") (name "Net-(U10B-OUT)") (class "Default")
      (node (ref "PORTC") (pin "7") (pinfunction "7_7") (pintype "passive"))
      (node (ref "U10") (pin "7") (pinfunction "OUT_7") (pintype "output"))
      (node (ref "U5") (pin "7") (pinfunction "O_7") (pintype "output"))
      (node (ref "X3") (pin "5") (pinfunction "5_5") (pintype "passive"))
    )
    (net (code "110") (name "Net-(U10C-OUT)") (class "Default")
      (node (ref "PORTC") (pin "8") (pinfunction "8_8") (pintype "passive"))
      (node (ref "U10") (pin "8") (pinfunction "OUT_8") (pintype "output"))
      (node (ref "U5") (pin "5") (pinfunction "O_5") (pintype "output"))
      (node (ref "X3") (pin "6") (pinfunction "6_6") (pintype "passive"))
    )
    (net (code "111") (name "Net-(U10D-OUT)") (class "Default")
      (node (ref "PORTC") (pin "10") (pinfunction "10_10") (pintype "passive"))
      (node (ref "U10") (pin "14") (pinfunction "OUT_14") (pintype "output"))
      (node (ref "U6") (pin "7") (pinfunction "O_7") (pintype "output"))
      (node (ref "X3") (pin "8") (pinfunction "8_8") (pintype "passive"))
    )
    (net (code "112") (name "Net-(U11A-QA)") (class "Default")
      (node (ref "R3") (pin "1") (pinfunction "1_1") (pintype "passive"))
      (node (ref "U11") (pin "15") (pinfunction "QA_15") (pintype "tri_state"))
      (node (ref "U12") (pin "1") (pinfunction "I1_1") (pintype "input"))
    )
    (net (code "113") (name "Net-(U11A-QB)") (class "Default")
      (node (ref "R4") (pin "1") (pinfunction "1_1") (pintype "passive"))
      (node (ref "U11") (pin "1") (pinfunction "QB_1") (pintype "tri_state"))
      (node (ref "U12") (pin "2") (pinfunction "I2_2") (pintype "input"))
    )
    (net (code "114") (name "Net-(U11A-QC)") (class "Default")
      (node (ref "R5") (pin "1") (pinfunction "1_1") (pintype "passive"))
      (node (ref "U11") (pin "2") (pinfunction "QC_2") (pintype "tri_state"))
      (node (ref "U12") (pin "3") (pinfunction "I3_3") (pintype "input"))
    )
    (net (code "115") (name "Net-(U11A-QD)") (class "Default")
      (node (ref "R6") (pin "1") (pinfunction "1_1") (pintype "passive"))
      (node (ref "U11") (pin "3") (pinfunction "QD_3") (pintype "tri_state"))
      (node (ref "U12") (pin "4") (pinfunction "I4_4") (pintype "input"))
    )
    (net (code "116") (name "Net-(U11A-QE)") (class "Default")
      (node (ref "R7") (pin "1") (pinfunction "1_1") (pintype "passive"))
      (node (ref "U11") (pin "4") (pinfunction "QE_4") (pintype "tri_state"))
      (node (ref "U12") (pin "5") (pinfunction "I5_5") (pintype "input"))
    )
    (net (code "117") (name "Net-(U11A-QF)") (class "Default")
      (node (ref "R8") (pin "1") (pinfunction "1_1") (pintype "passive"))
      (node (ref "U11") (pin "5") (pinfunction "QF_5") (pintype "tri_state"))
      (node (ref "U12") (pin "6") (pinfunction "I6_6") (pintype "input"))
    )
    (net (code "118") (name "Net-(U11A-QG)") (class "Default")
      (node (ref "R9") (pin "1") (pinfunction "1_1") (pintype "passive"))
      (node (ref "U11") (pin "6") (pinfunction "QG_6") (pintype "tri_state"))
      (node (ref "U12") (pin "7") (pinfunction "I7_7") (pintype "input"))
    )
    (net (code "119") (name "Net-(U11A-QH)") (class "Default")
      (node (ref "R10") (pin "1") (pinfunction "1_1") (pintype "passive"))
      (node (ref "U11") (pin "7") (pinfunction "QH_7") (pintype "tri_state"))
      (node (ref "U12") (pin "8") (pinfunction "I8_8") (pintype "input"))
    )
    (net (code "120") (name "Net-(U13A-QA)") (class "Default")
      (node (ref "R11") (pin "1") (pinfunction "1_1") (pintype "passive"))
      (node (ref "U13") (pin "15") (pinfunction "QA_15") (pintype "tri_state"))
      (node (ref "U14") (pin "1") (pinfunction "I1_1") (pintype "input"))
    )
    (net (code "121") (name "Net-(U13A-QB)") (class "Default")
      (node (ref "R12") (pin "1") (pinfunction "1_1") (pintype "passive"))
      (node (ref "U13") (pin "1") (pinfunction "QB_1") (pintype "tri_state"))
      (node (ref "U14") (pin "2") (pinfunction "I2_2") (pintype "input"))
    )
    (net (code "122") (name "Net-(U13A-QC)") (class "Default")
      (node (ref "R13") (pin "1") (pinfunction "1_1") (pintype "passive"))
      (node (ref "U13") (pin "2") (pinfunction "QC_2") (pintype "tri_state"))
      (node (ref "U14") (pin "3") (pinfunction "I3_3") (pintype "input"))
    )
    (net (code "123") (name "Net-(U13A-QD)") (class "Default")
      (node (ref "R14") (pin "1") (pinfunction "1_1") (pintype "passive"))
      (node (ref "U13") (pin "3") (pinfunction "QD_3") (pintype "tri_state"))
      (node (ref "U14") (pin "4") (pinfunction "I4_4") (pintype "input"))
    )
    (net (code "124") (name "Net-(U13A-QE)") (class "Default")
      (node (ref "R15") (pin "1") (pinfunction "1_1") (pintype "passive"))
      (node (ref "U13") (pin "4") (pinfunction "QE_4") (pintype "tri_state"))
      (node (ref "U14") (pin "5") (pinfunction "I5_5") (pintype "input"))
    )
    (net (code "125") (name "Net-(U13A-QF)") (class "Default")
      (node (ref "R16") (pin "1") (pinfunction "1_1") (pintype "passive"))
      (node (ref "U13") (pin "5") (pinfunction "QF_5") (pintype "tri_state"))
      (node (ref "U14") (pin "6") (pinfunction "I6_6") (pintype "input"))
    )
    (net (code "126") (name "Net-(U13A-QG)") (class "Default")
      (node (ref "R17") (pin "1") (pinfunction "1_1") (pintype "passive"))
      (node (ref "U13") (pin "6") (pinfunction "QG_6") (pintype "tri_state"))
      (node (ref "U14") (pin "7") (pinfunction "I7_7") (pintype "input"))
    )
    (net (code "127") (name "Net-(U13A-QH)") (class "Default")
      (node (ref "R18") (pin "1") (pinfunction "1_1") (pintype "passive"))
      (node (ref "U13") (pin "7") (pinfunction "QH_7") (pintype "tri_state"))
      (node (ref "U14") (pin "8") (pinfunction "I8_8") (pintype "input"))
    )
    (net (code "128") (name "OLAT") (class "Default")
      (node (ref "R21") (pin "1") (pinfunction "1_1") (pintype "passive"))
      (node (ref "U$1") (pin "PA8") (pinfunction "PA8_PA8") (pintype "bidirectional"))
      (node (ref "U11") (pin "12") (pinfunction "RCK_12") (pintype "input"))
      (node (ref "U13") (pin "12") (pinfunction "RCK_12") (pintype "input"))
    )
    (net (code "129") (name "SCK") (class "Default")
      (node (ref "JP2") (pin "3") (pinfunction "3_3") (pintype "passive"))
      (node (ref "R19") (pin "1") (pinfunction "1_1") (pintype "passive"))
      (node (ref "U$1") (pin "PB3") (pinfunction "PB3_PB3") (pintype "bidirectional"))
      (node (ref "U11") (pin "11") (pinfunction "SCK_11") (pintype "input"))
      (node (ref "U13") (pin "11") (pinfunction "SCK_11") (pintype "input"))
    )
    (net (code "130") (name "SCK2") (class "Default")
      (node (ref "U$1") (pin "PB10") (pinfunction "PB10_PB10") (pintype "bidirectional"))
      (node (ref "U1") (pin "7") (pinfunction "CLK_7") (pintype "input"))
      (node (ref "U2") (pin "7") (pinfunction "CLK_7") (pintype "input"))
    )
    (net (code "131") (name "SLNK1") (class "Default")
      (node (ref "SJ17") (pin "P$1") (pinfunction "1_P$1") (pintype "passive"))
      (node (ref "U11") (pin "9") (pinfunction "QH*_9") (pintype "tri_state"))
      (node (ref "U13") (pin "14") (pinfunction "SER_14") (pintype "input"))
    )
    (net (code "132") (name "SLNK2") (class "Default")
      (node (ref "SJ16") (pin "P$1") (pinfunction "1_P$1") (pintype "passive"))
      (node (ref "U13") (pin "9") (pinfunction "QH*_9") (pintype "tri_state"))
    )
    (net (code "133") (name "SLNK3") (class "Default")
      (node (ref "U1") (pin "13") (pinfunction "QH_13") (pintype "output"))
      (node (ref "U2") (pin "1") (pinfunction "SER_1") (pintype "input"))
    )
    (net (code "134") (name "SRV1") (class "Default")
      (node (ref "JP5") (pin "2") (pinfunction "2_2") (pintype "passive"))
      (node (ref "R24") (pin "2") (pinfunction "2_2") (pintype "passive"))
      (node (ref "U$1") (pin "PC9") (pinfunction "PC9_PC9") (pintype "bidirectional"))
    )
    (net (code "135") (name "SRV2") (class "Default")
      (node (ref "JP5") (pin "1") (pinfunction "1_1") (pintype "passive"))
      (node (ref "R25") (pin "2") (pinfunction "2_2") (pintype "passive"))
      (node (ref "U$1") (pin "PC7") (pinfunction "PC7_PC7") (pintype "bidirectional"))
    )
    (net (code "136") (name "SRV3") (class "Default")
      (node (ref "JP6") (pin "2") (pinfunction "2_2") (pintype "passive"))
      (node (ref "R26") (pin "2") (pinfunction "2_2") (pintype "passive"))
      (node (ref "U$1") (pin "PC8") (pinfunction "PC8_PC8") (pintype "bidirectional"))
    )
    (net (code "137") (name "SRV4") (class "Default")
      (node (ref "JP6") (pin "1") (pinfunction "1_1") (pintype "passive"))
      (node (ref "R27") (pin "2") (pinfunction "2_2") (pintype "passive"))
      (node (ref "U$1") (pin "PC6") (pinfunction "PC6_PC6") (pintype "bidirectional"))
    )
    (net (code "138") (name "SRV5") (class "Default")
      (node (ref "JP7") (pin "2") (pinfunction "2_2") (pintype "passive"))
      (node (ref "R64") (pin "2") (pinfunction "2_2") (pintype "passive"))
      (node (ref "U$1") (pin "PF1-PH1") (pinfunction "PF1-PH1_PF1-PH1") (pintype "bidirectional"))
    )
    (net (code "139") (name "SRV6") (class "Default")
      (node (ref "JP7") (pin "1") (pinfunction "1_1") (pintype "passive"))
      (node (ref "R65") (pin "2") (pinfunction "2_2") (pintype "passive"))
      (node (ref "U$1") (pin "PA15") (pinfunction "PA15_PA15") (pintype "bidirectional"))
    )
    (net (code "140") (name "SRV7") (class "Default")
      (node (ref "JP8") (pin "2") (pinfunction "2_2") (pintype "passive"))
      (node (ref "R66") (pin "2") (pinfunction "2_2") (pintype "passive"))
      (node (ref "U$1") (pin "PC12") (pinfunction "PC12_PC12") (pintype "bidirectional"))
    )
    (net (code "141") (name "SRV8") (class "Default")
      (node (ref "JP8") (pin "1") (pinfunction "1_1") (pintype "passive"))
      (node (ref "R67") (pin "2") (pinfunction "2_2") (pintype "passive"))
      (node (ref "U$1") (pin "PD2") (pinfunction "PD2_PD2") (pintype "bidirectional"))
    )
    (net (code "142") (name "TDRV1") (class "Default")
      (node (ref "U$1") (pin "PB12") (pinfunction "PB12_PB12") (pintype "bidirectional"))
      (node (ref "U10") (pin "12") (pinfunction "+IN_12") (pintype "input"))
      (node (ref "U6") (pin "2") (pinfunction "I_2") (pintype "input"))
    )
    (net (code "143") (name "TDRV2") (class "Default")
      (node (ref "U$1") (pin "PB2") (pinfunction "PB2_PB2") (pintype "bidirectional"))
      (node (ref "U10") (pin "3") (pinfunction "+IN_3") (pintype "input"))
      (node (ref "U6") (pin "4") (pinfunction "I_4") (pintype "input"))
    )
    (net (code "144") (name "TDRV3") (class "Default")
      (node (ref "U$1") (pin "PB15") (pinfunction "PB15_PB15") (pintype "bidirectional"))
      (node (ref "U10") (pin "10") (pinfunction "+IN_10") (pintype "input"))
      (node (ref "U5") (pin "4") (pinfunction "I_4") (pintype "input"))
    )
    (net (code "145") (name "TDRV4") (class "Default")
      (node (ref "U$1") (pin "PB1") (pinfunction "PB1_PB1") (pintype "bidirectional"))
      (node (ref "U10") (pin "5") (pinfunction "+IN_5") (pintype "input"))
      (node (ref "U5") (pin "2") (pinfunction "I_2") (pintype "input"))
    )
    (net (code "146") (name "TDRV5") (class "Default")
      (node (ref "U$1") (pin "PA0") (pinfunction "PA0_PA0") (pintype "bidirectional"))
      (node (ref "U4") (pin "2") (pinfunction "I_2") (pintype "input"))
      (node (ref "U9") (pin "12") (pinfunction "+IN_12") (pintype "input"))
    )
    (net (code "147") (name "TDRV6") (class "Default")
      (node (ref "U$1") (pin "PA4") (pinfunction "PA4_PA4") (pintype "bidirectional"))
      (node (ref "U4") (pin "4") (pinfunction "I_4") (pintype "input"))
      (node (ref "U9") (pin "3") (pinfunction "+IN_3") (pintype "input"))
    )
    (net (code "148") (name "TDRV7") (class "Default")
      (node (ref "U$1") (pin "PC3") (pinfunction "PC3_PC3") (pintype "bidirectional"))
      (node (ref "U3") (pin "4") (pinfunction "I_4") (pintype "input"))
      (node (ref "U9") (pin "10") (pinfunction "+IN_10") (pintype "input"))
    )
    (net (code "149") (name "TDRV8") (class "Default")
      (node (ref "U$1") (pin "PC0") (pinfunction "PC0_PC0") (pintype "bidirectional"))
      (node (ref "U3") (pin "2") (pinfunction "I_2") (pintype "input"))
      (node (ref "U9") (pin "5") (pinfunction "+IN_5") (pintype "input"))
    )
    (net (code "150") (name "V+") (class "Default")
      (node (ref "C1") (pin "1") (pinfunction "1_1") (pintype "passive"))
      (node (ref "C2") (pin "+") (pinfunction "+_+") (pintype "passive"))
      (node (ref "L1") (pin "1") (pinfunction "1_1") (pintype "passive"))
      (node (ref "U$1") (pin "E5V") (pinfunction "E5V_E5V") (pintype "power_in"))
      (node (ref "U8") (pin "3") (pinfunction "FB_3") (pintype "bidirectional"))
      (node (ref "U8B") (pin "1") (pinfunction "FB_1") (pintype "input"))
    )
    (net (code "151") (name "unconnected-(H1-MOUNT-PadB3,3)") (class "Default")
      (node (ref "H1") (pin "B3,3") (pinfunction "MOUNT_B3,3") (pintype "passive"))
    )
    (net (code "152") (name "unconnected-(H2-MOUNT-PadB3,3)") (class "Default")
      (node (ref "H2") (pin "B3,3") (pinfunction "MOUNT_B3,3") (pintype "passive"))
    )
    (net (code "153") (name "unconnected-(H3-MOUNT-PadB3,3)") (class "Default")
      (node (ref "H3") (pin "B3,3") (pinfunction "MOUNT_B3,3") (pintype "passive"))
    )
    (net (code "154") (name "unconnected-(H4-MOUNT-PadB3,3)") (class "Default")
      (node (ref "H4") (pin "B3,3") (pinfunction "MOUNT_B3,3") (pintype "passive"))
    )
    (net (code "155") (name "unconnected-(U$1-PadBOOT0)") (class "Default")
      (node (ref "U$1") (pin "BOOT0") (pinfunction "BOOT0_BOOT0") (pintype "bidirectional"))
    )
    (net (code "156") (name "unconnected-(U$1-PadIOREF2)") (class "Default")
      (node (ref "U$1") (pin "IOREF2") (pinfunction "IOREF2_IOREF2") (pintype "input"))
    )
    (net (code "157") (name "unconnected-(U$1-PadNC1-PF7)") (class "Default")
      (node (ref "U$1") (pin "NC1-PF7") (pinfunction "NC1-PF7_NC1-PF7") (pintype "bidirectional"))
    )
    (net (code "158") (name "unconnected-(U$1-PadNC2-PF6)") (class "Default")
      (node (ref "U$1") (pin "NC2-PF6") (pinfunction "NC2-PF6_NC2-PF6") (pintype "bidirectional"))
    )
    (net (code "159") (name "unconnected-(U$1-PadNC3)") (class "Default")
      (node (ref "U$1") (pin "NC3") (pinfunction "NC3_NC3") (pintype "no_connect"))
    )
    (net (code "160") (name "unconnected-(U$1-PadNC4)") (class "Default")
      (node (ref "U$1") (pin "NC4") (pinfunction "NC4_NC4") (pintype "no_connect"))
    )
    (net (code "161") (name "unconnected-(U$1-PadNC5-PD8)") (class "Default")
      (node (ref "U$1") (pin "NC5-PD8") (pinfunction "NC5-PD8_NC5-PD8") (pintype "bidirectional"))
    )
    (net (code "162") (name "unconnected-(U$1-PadNC6-PB11)") (class "Default")
      (node (ref "U$1") (pin "NC6-PB11") (pinfunction "NC6-PB11_NC6-PB11") (pintype "no_connect"))
    )
    (net (code "163") (name "unconnected-(U$1-PadNC7-PF5)") (class "Default")
      (node (ref "U$1") (pin "NC7-PF5") (pinfunction "NC7-PF5_NC7-PF5") (pintype "bidirectional"))
    )
    (net (code "164") (name "unconnected-(U$1-PadNC8-PF4)") (class "Default")
      (node (ref "U$1") (pin "NC8-PF4") (pinfunction "NC8-PF4_NC8-PF4") (pintype "bidirectional"))
    )
    (net (code "165") (name "unconnected-(U$1-PadNRESET)") (class "Default")
      (node (ref "U$1") (pin "NRESET") (pinfunction "NRESET_NRESET") (pintype "input"))
    )
    (net (code "166") (name "unconnected-(U$1-PadPA1)") (class "Default")
      (node (ref "U$1") (pin "PA1") (pinfunction "PA1_PA1") (pintype "bidirectional"))
    )
    (net (code "167") (name "unconnected-(U$1-PadPA2)") (class "Default")
      (node (ref "U$1") (pin "PA2") (pinfunction "PA2_PA2") (pintype "bidirectional"))
    )
    (net (code "168") (name "unconnected-(U$1-PadPA3)") (class "Default")
      (node (ref "U$1") (pin "PA3") (pinfunction "PA3_PA3") (pintype "bidirectional"))
    )
    (net (code "169") (name "unconnected-(U$1-PadPA5)") (class "Default")
      (node (ref "U$1") (pin "PA5") (pinfunction "PA5_PA5") (pintype "bidirectional"))
    )
    (net (code "170") (name "unconnected-(U$1-PadPA7)") (class "Default")
      (node (ref "U$1") (pin "PA7") (pinfunction "PA7_PA7") (pintype "bidirectional"))
    )
    (net (code "171") (name "unconnected-(U$1-PadPA9)") (class "Default")
      (node (ref "U$1") (pin "PA9") (pinfunction "PA9_PA9") (pintype "bidirectional"))
    )
    (net (code "172") (name "unconnected-(U$1-PadPA10)") (class "Default")
      (node (ref "U$1") (pin "PA10") (pinfunction "PA10_PA10") (pintype "bidirectional"))
    )
    (net (code "173") (name "unconnected-(U$1-PadPA11)") (class "Default")
      (node (ref "U$1") (pin "PA11") (pinfunction "PA11_PA11") (pintype "bidirectional"))
    )
    (net (code "174") (name "unconnected-(U$1-PadPA12)") (class "Default")
      (node (ref "U$1") (pin "PA12") (pinfunction "PA12_PA12") (pintype "bidirectional"))
    )
    (net (code "175") (name "unconnected-(U$1-PadPA13)") (class "Default")
      (node (ref "U$1") (pin "PA13") (pinfunction "PA13_PA13") (pintype "bidirectional"))
    )
    (net (code "176") (name "unconnected-(U$1-PadPA14)") (class "Default")
      (node (ref "U$1") (pin "PA14") (pinfunction "PA14_PA14") (pintype "bidirectional"))
    )
    (net (code "177") (name "unconnected-(U$1-PadPB0)") (class "Default")
      (node (ref "U$1") (pin "PB0") (pinfunction "PB0_PB0") (pintype "bidirectional"))
    )
    (net (code "178") (name "unconnected-(U$1-PadPB13)") (class "Default")
      (node (ref "U$1") (pin "PB13") (pinfunction "PB13_PB13") (pintype "bidirectional"))
    )
    (net (code "179") (name "unconnected-(U$1-PadPC1)") (class "Default")
      (node (ref "U$1") (pin "PC1") (pinfunction "PC1_PC1") (pintype "bidirectional"))
    )
    (net (code "180") (name "unconnected-(U$1-PadPC4)") (class "Default")
      (node (ref "U$1") (pin "PC4") (pinfunction "PC4_PC4") (pintype "bidirectional"))
    )
    (net (code "181") (name "unconnected-(U$1-PadPC5)") (class "Default")
      (node (ref "U$1") (pin "PC5") (pinfunction "PC5_PC5") (pintype "bidirectional"))
    )
    (net (code "182") (name "unconnected-(U$1-PadPC13)") (class "Default")
      (node (ref "U$1") (pin "PC13") (pinfunction "PC13_PC13") (pintype "bidirectional"))
    )
    (net (code "183") (name "unconnected-(U$1-PadPC14)") (class "Default")
      (node (ref "U$1") (pin "PC14") (pinfunction "PC14_PC14") (pintype "bidirectional"))
    )
    (net (code "184") (name "unconnected-(U$1-PadPC15)") (class "Default")
      (node (ref "U$1") (pin "PC15") (pinfunction "PC15_PC15") (pintype "bidirectional"))
    )
    (net (code "185") (name "unconnected-(U$1-PadPF0-PH0)") (class "Default")
      (node (ref "U$1") (pin "PF0-PH0") (pinfunction "PF0-PH0_PF0-PH0") (pintype "bidirectional"))
    )
  )
)
